# frontplatine_v0_2_230121.net
KiCad netlist of a schematic drawn in EAGLE
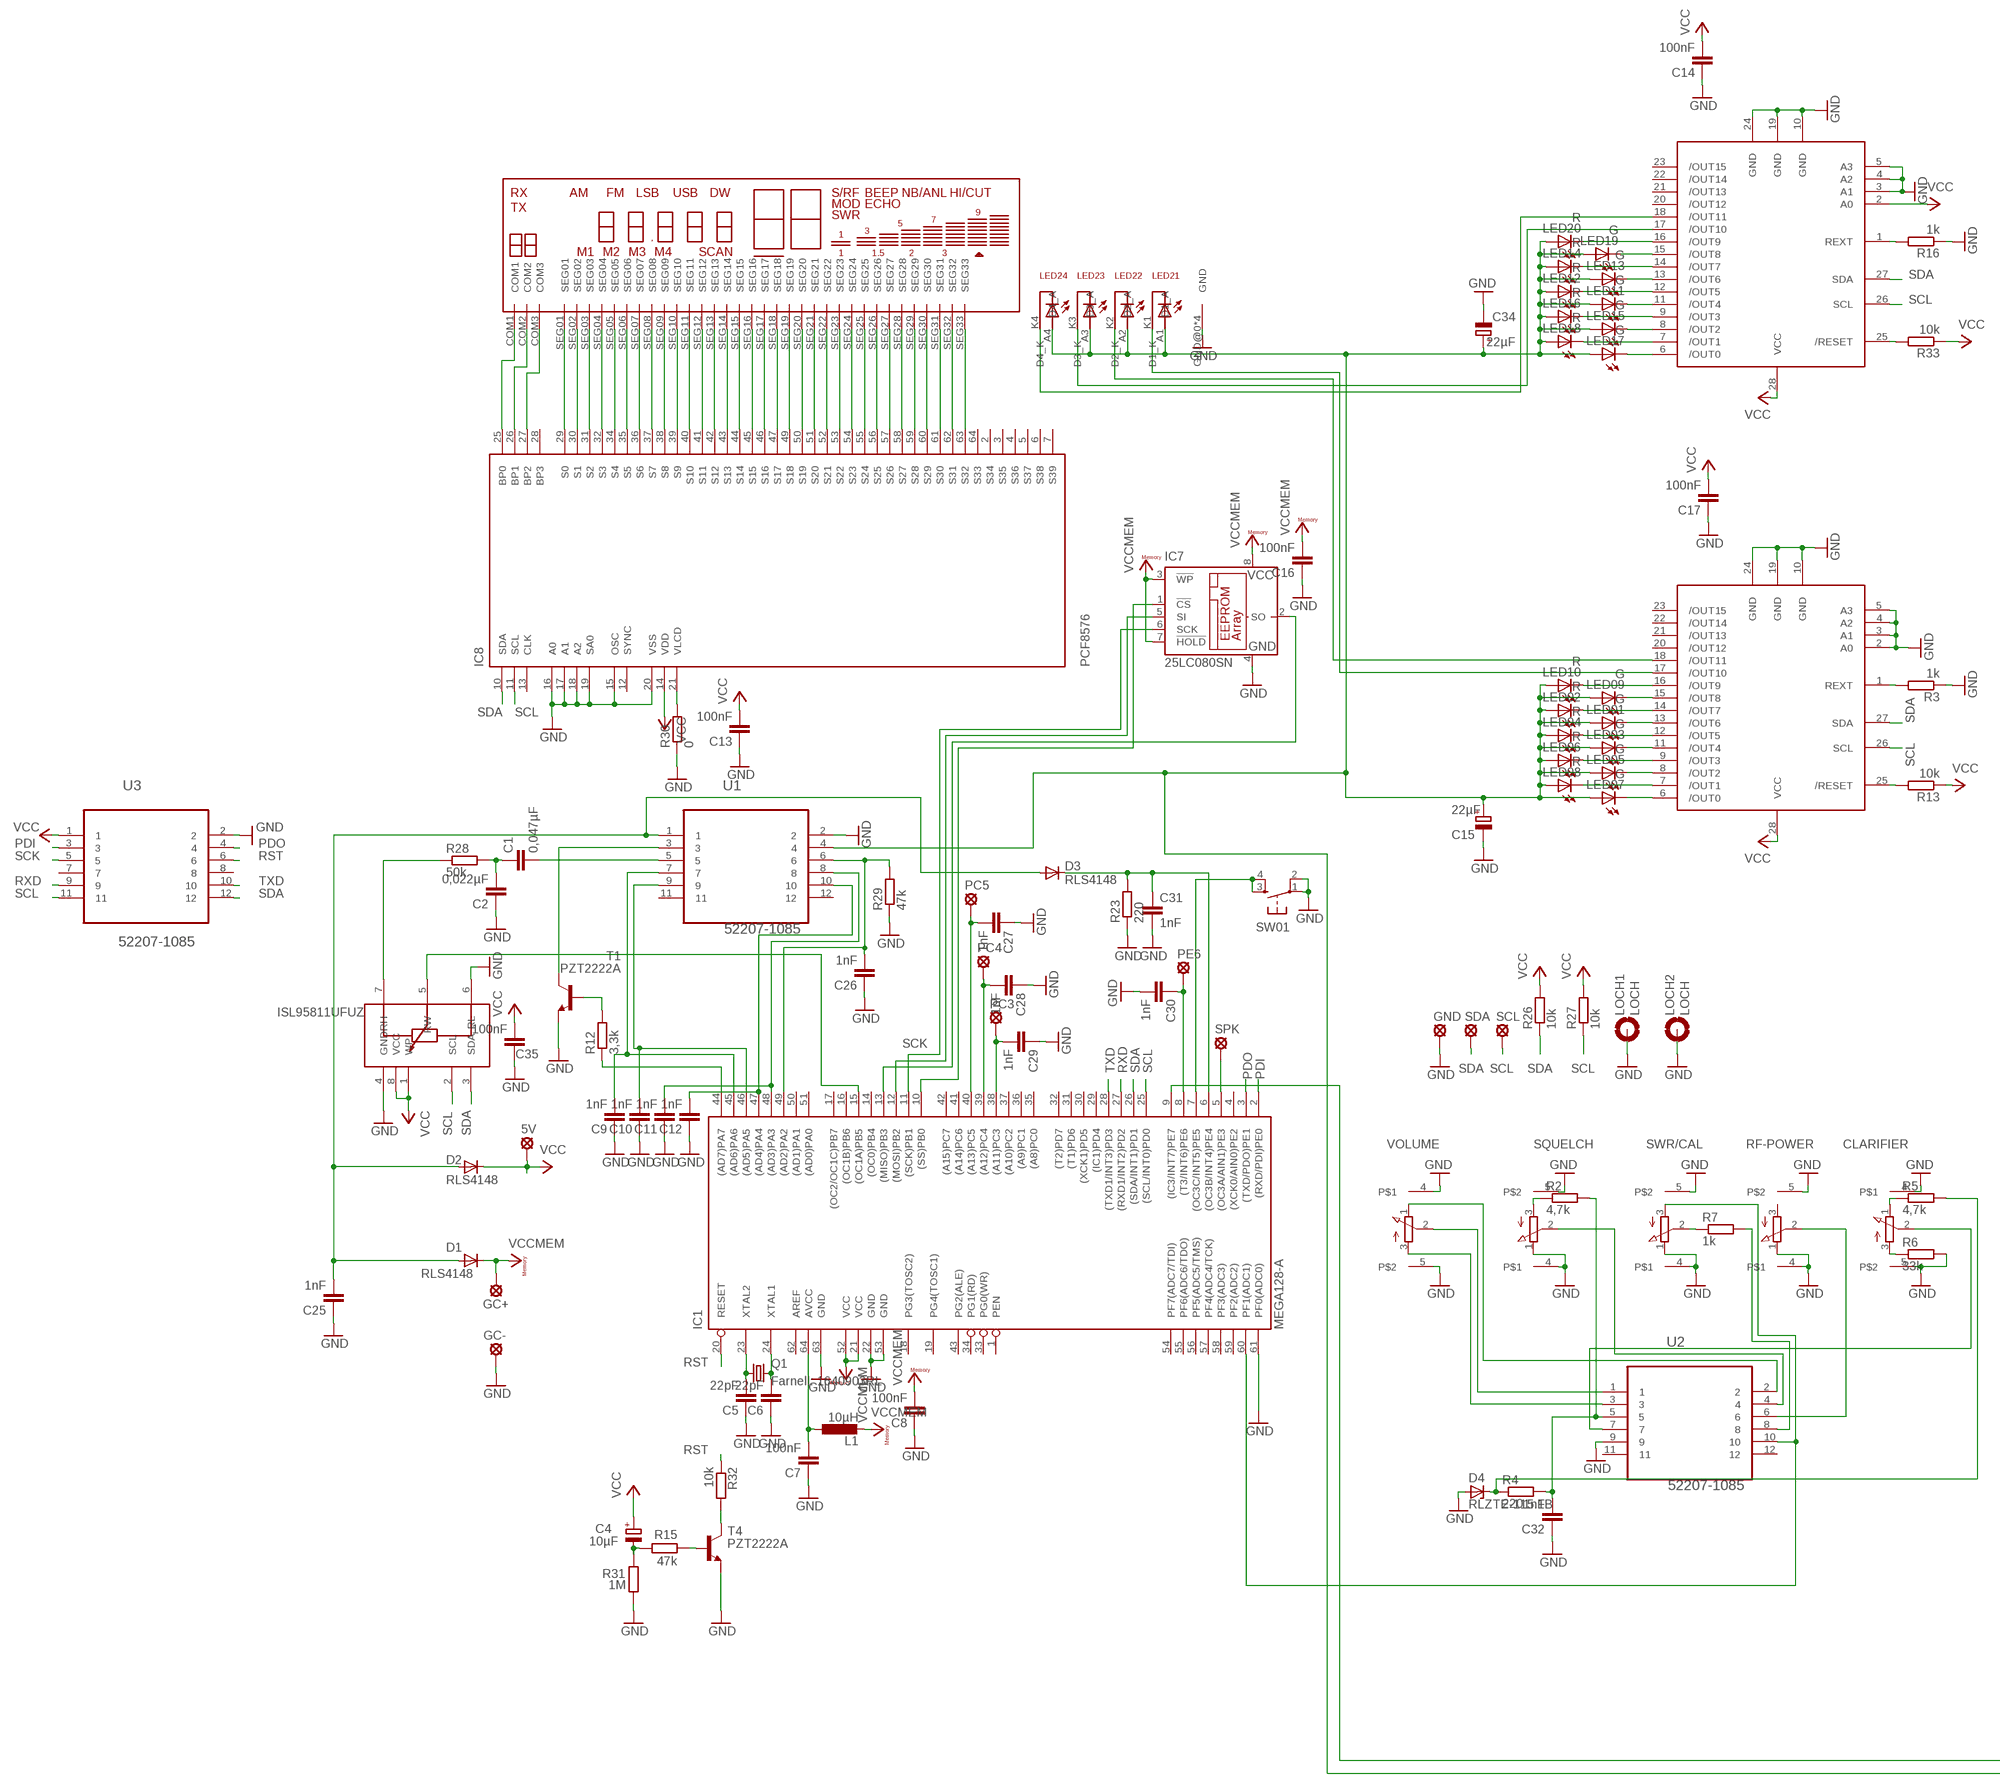
[diagram p0: schematic, sheet 1, part 1 of 2]
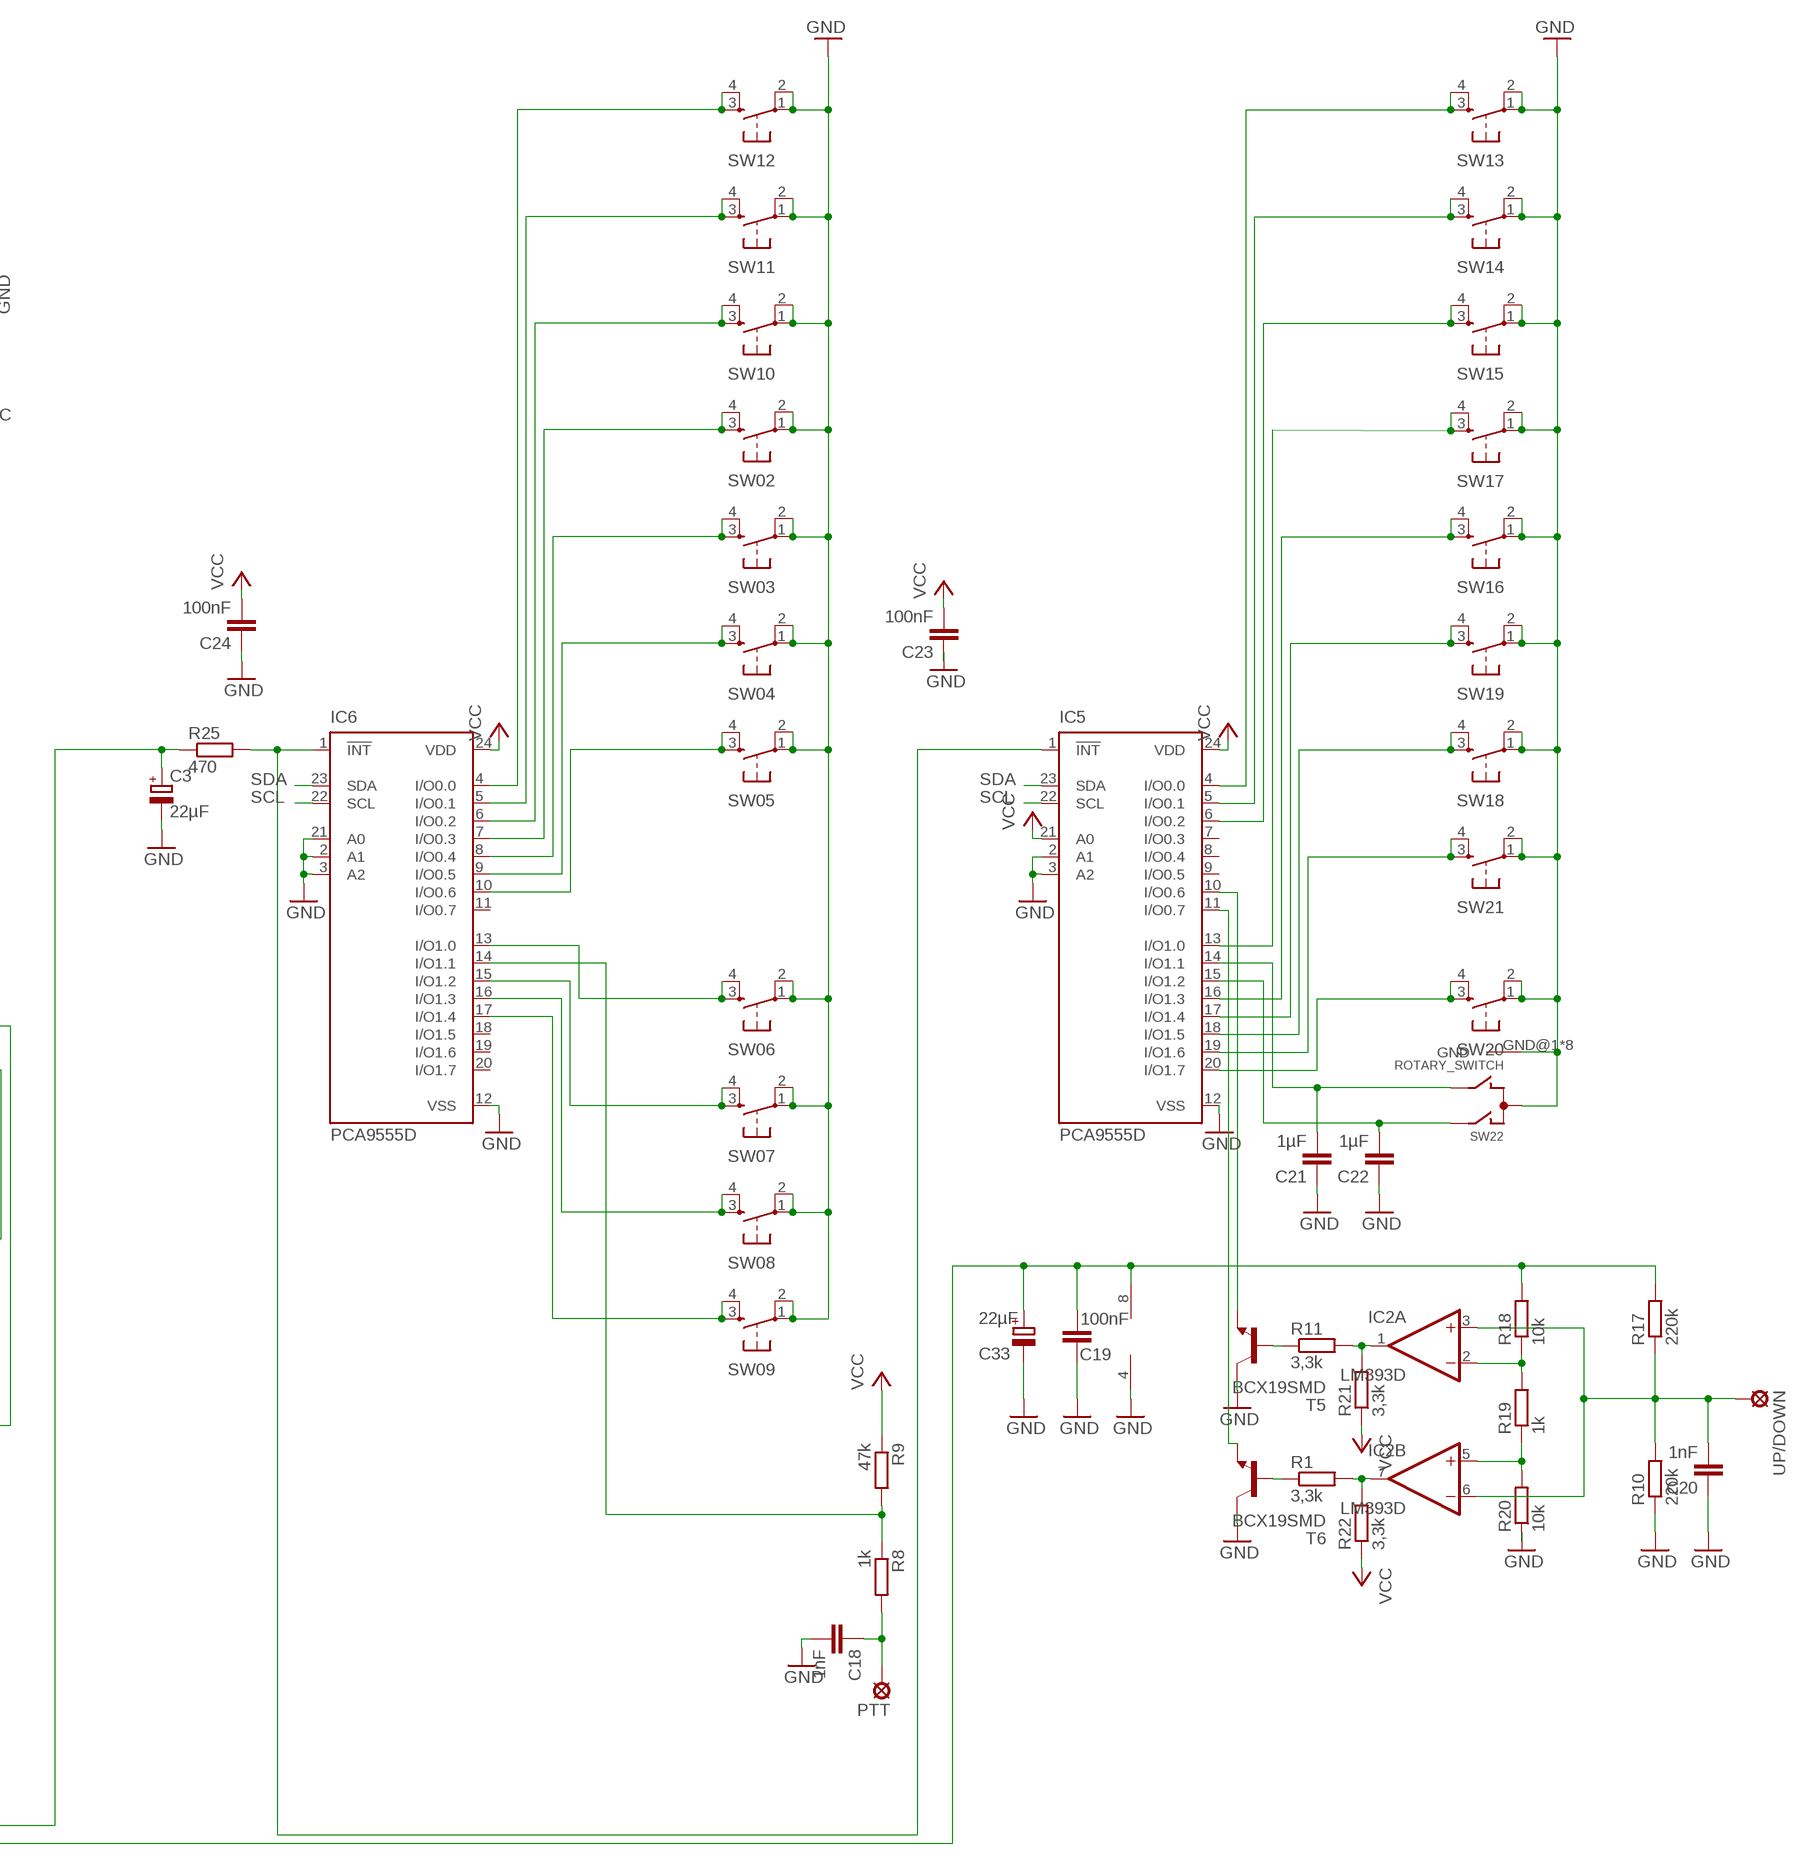
[diagram p1: schematic, sheet 1, part 2 of 2]

(export (version "E")
  (design (tool "Eeschema 10.0.6"))
  (components
    (comp (ref "5V")
      (value "SE11")
      (footprint "eagle-import:SE11")
      (libsource (lib "eagle-import") (part "SE11"))
    )
    (comp (ref "C1")
      (value "0,047µF")
      (footprint "eagle-import:C1206")
      (libsource (lib "eagle-import") (part "C-EUC1206"))
    )
    (comp (ref "C2")
      (value "0,022µF")
      (footprint "eagle-import:C1206")
      (libsource (lib "eagle-import") (part "resistor_C-EUC1206"))
    )
    (comp (ref "C3")
      (value "22µF")
      (footprint "eagle-import:CT3216")
      (libsource (lib "eagle-import") (part "CPOL-EUCT3216"))
    )
    (comp (ref "C4")
      (value "10µF")
      (footprint "eagle-import:CT3216")
      (libsource (lib "eagle-import") (part "CPOL-EUCT3216"))
    )
    (comp (ref "C5")
      (value "22pF")
      (footprint "eagle-import:C1206")
      (libsource (lib "eagle-import") (part "resistor_C-EUC1206"))
    )
    (comp (ref "C6")
      (value "22pF")
      (footprint "eagle-import:C1206")
      (libsource (lib "eagle-import") (part "resistor_C-EUC1206"))
    )
    (comp (ref "C7")
      (value "100nF")
      (footprint "eagle-import:C1206")
      (libsource (lib "eagle-import") (part "resistor_C-EUC1206"))
    )
    (comp (ref "C8")
      (value "100nF")
      (footprint "eagle-import:C1206")
      (libsource (lib "eagle-import") (part "resistor_C-EUC1206"))
    )
    (comp (ref "C9")
      (value "1nF")
      (footprint "eagle-import:C1206")
      (libsource (lib "eagle-import") (part "resistor_C-EUC1206"))
    )
    (comp (ref "C10")
      (value "1nF")
      (footprint "eagle-import:C1206")
      (libsource (lib "eagle-import") (part "resistor_C-EUC1206"))
    )
    (comp (ref "C11")
      (value "1nF")
      (footprint "eagle-import:C1206")
      (libsource (lib "eagle-import") (part "resistor_C-EUC1206"))
    )
    (comp (ref "C12")
      (value "1nF")
      (footprint "eagle-import:C1206")
      (libsource (lib "eagle-import") (part "resistor_C-EUC1206"))
    )
    (comp (ref "C13")
      (value "100nF")
      (footprint "eagle-import:C1206")
      (libsource (lib "eagle-import") (part "resistor_C-EUC1206"))
    )
    (comp (ref "C14")
      (value "100nF")
      (footprint "eagle-import:C1206")
      (libsource (lib "eagle-import") (part "resistor_C-EUC1206"))
    )
    (comp (ref "C15")
      (value "22µF")
      (footprint "eagle-import:CT3216")
      (libsource (lib "eagle-import") (part "CPOL-EUCT3216"))
    )
    (comp (ref "C16")
      (value "100nF")
      (footprint "eagle-import:C1206")
      (libsource (lib "eagle-import") (part "resistor_C-EUC1206"))
    )
    (comp (ref "C17")
      (value "100nF")
      (footprint "eagle-import:C1206")
      (libsource (lib "eagle-import") (part "resistor_C-EUC1206"))
    )
    (comp (ref "C18")
      (value "1nF")
      (footprint "eagle-import:C1206")
      (libsource (lib "eagle-import") (part "resistor_C-EUC1206"))
    )
    (comp (ref "C19")
      (value "100nF")
      (footprint "eagle-import:C1206")
      (libsource (lib "eagle-import") (part "resistor_C-EUC1206"))
    )
    (comp (ref "C20")
      (value "1nF")
      (footprint "eagle-import:C1206")
      (libsource (lib "eagle-import") (part "resistor_C-EUC1206"))
    )
    (comp (ref "C21")
      (value "1µF")
      (footprint "eagle-import:C1206")
      (libsource (lib "eagle-import") (part "resistor_C-EUC1206"))
    )
    (comp (ref "C22")
      (value "1µF")
      (footprint "eagle-import:C1206")
      (libsource (lib "eagle-import") (part "resistor_C-EUC1206"))
    )
    (comp (ref "C23")
      (value "100nF")
      (footprint "eagle-import:C1206")
      (libsource (lib "eagle-import") (part "resistor_C-EUC1206"))
    )
    (comp (ref "C24")
      (value "100nF")
      (footprint "eagle-import:C1206")
      (libsource (lib "eagle-import") (part "resistor_C-EUC1206"))
    )
    (comp (ref "C25")
      (value "1nF")
      (footprint "eagle-import:C1206")
      (libsource (lib "eagle-import") (part "resistor_C-EUC1206"))
    )
    (comp (ref "C26")
      (value "1nF")
      (footprint "eagle-import:C1206")
      (libsource (lib "eagle-import") (part "resistor_C-EUC1206"))
    )
    (comp (ref "C27")
      (value "1nF")
      (footprint "eagle-import:C1206")
      (libsource (lib "eagle-import") (part "resistor_C-EUC1206"))
    )
    (comp (ref "C28")
      (value "1nF")
      (footprint "eagle-import:C1206")
      (libsource (lib "eagle-import") (part "resistor_C-EUC1206"))
    )
    (comp (ref "C29")
      (value "1nF")
      (footprint "eagle-import:C1206")
      (libsource (lib "eagle-import") (part "resistor_C-EUC1206"))
    )
    (comp (ref "C30")
      (value "1nF")
      (footprint "eagle-import:C1206")
      (libsource (lib "eagle-import") (part "resistor_C-EUC1206"))
    )
    (comp (ref "C31")
      (value "1nF")
      (footprint "eagle-import:C1206")
      (libsource (lib "eagle-import") (part "resistor_C-EUC1206"))
    )
    (comp (ref "C32")
      (value "1nF")
      (footprint "eagle-import:C1206")
      (libsource (lib "eagle-import") (part "resistor_C-EUC1206"))
    )
    (comp (ref "C33")
      (value "22µF")
      (footprint "eagle-import:CT3216")
      (libsource (lib "eagle-import") (part "CPOL-EUCT3216"))
    )
    (comp (ref "C34")
      (value "22µF")
      (footprint "eagle-import:CT3216")
      (libsource (lib "eagle-import") (part "CPOL-EUCT3216"))
    )
    (comp (ref "C35")
      (value "100nF")
      (footprint "eagle-import:C1206")
      (libsource (lib "eagle-import") (part "resistor_C-EUC1206"))
    )
    (comp (ref "CLARIFIER")
      (value "POTI")
      (footprint "eagle-import:POTI")
      (libsource (lib "eagle-import") (part "POTI"))
    )
    (comp (ref "D1")
      (value "RLS4148")
      (footprint "eagle-import:SOD80C")
      (libsource (lib "eagle-import") (part "DIODE-SOD80C"))
    )
    (comp (ref "D2")
      (value "RLS4148")
      (footprint "eagle-import:SOD80C")
      (libsource (lib "eagle-import") (part "DIODE-SOD80C"))
    )
    (comp (ref "D3")
      (value "RLS4148")
      (footprint "eagle-import:SOD80C")
      (libsource (lib "eagle-import") (part "DIODE-SOD80C"))
    )
    (comp (ref "D4")
      (value "RLZTE-115.1B")
      (footprint "eagle-import:SOD80C")
      (libsource (lib "eagle-import") (part "ZENER-DIODESOD80C"))
    )
    (comp (ref "DISPLAY1")
      (value "DISPLAY")
      (footprint "eagle-import:DISPLAY")
      (libsource (lib "eagle-import") (part "DISPLAY"))
    )
    (comp (ref "GC+")
      (value "SE11")
      (footprint "eagle-import:SE11")
      (libsource (lib "eagle-import") (part "SE11"))
    )
    (comp (ref "GC-")
      (value "SE11")
      (footprint "eagle-import:SE11")
      (libsource (lib "eagle-import") (part "SE11"))
    )
    (comp (ref "GND")
      (value "SE11")
      (footprint "eagle-import:SE11")
      (libsource (lib "eagle-import") (part "SE11"))
    )
    (comp (ref "IC1")
      (value "MEGA128-A")
      (footprint "eagle-import:TQFP64")
      (fields (field (name "MPN") "ATMEGA128-16AU"))
      (libsource (lib "eagle-import") (part "MEGA128-A"))
    )
    (comp (ref "IC2")
      (value "LM393D")
      (footprint "eagle-import:SO08")
      (libsource (lib "eagle-import") (part "LM393D"))
    )
    (comp (ref "IC3")
      (value "TLC59116")
      (footprint "eagle-import:TSSOP28")
      (libsource (lib "eagle-import") (part "TLC59116"))
    )
    (comp (ref "IC4")
      (value "TLC59116")
      (footprint "eagle-import:TSSOP28")
      (libsource (lib "eagle-import") (part "TLC59116"))
    )
    (comp (ref "IC5")
      (value "PCA9555D")
      (footprint "eagle-import:SO24")
      (fields (field (name "MPN") "PCA9555DW"))
      (libsource (lib "eagle-import") (part "PCA9555D"))
    )
    (comp (ref "IC6")
      (value "PCA9555D")
      (footprint "eagle-import:SO24")
      (fields (field (name "MPN") "PCA9555DW"))
      (libsource (lib "eagle-import") (part "PCA9555D"))
    )
    (comp (ref "IC7")
      (value "25LC080SN")
      (footprint "eagle-import:SO-08")
      (fields
        (field (name "MF") "MICROCHIP")
        (field (name "MPN") "25LC080/SN")
        (field (name "MPN_1") "25LC080/SN")
        (field (name "OC_FARNELL") "1137302")
        (field (name "OC_NEWARK") "96K4092")
      )
      (libsource (lib "eagle-import") (part "25SNLC080"))
    )
    (comp (ref "IC8")
      (value "PCF8576")
      (footprint "eagle-import:LQFP-ST-64-2")
      (libsource (lib "eagle-import") (part "PCF8576"))
    )
    (comp (ref "L1")
      (value "10µH")
      (footprint "eagle-import:L1812")
      (libsource (lib "eagle-import") (part "L-EUL1812"))
    )
    (comp (ref "LED01")
      (value "G")
      (footprint "eagle-import:CHIPLED_1206")
      (libsource (lib "eagle-import") (part "LEDCHIPLED_1206"))
    )
    (comp (ref "LED02")
      (value "R")
      (footprint "eagle-import:CHIPLED_1206")
      (libsource (lib "eagle-import") (part "LEDCHIPLED_1206"))
    )
    (comp (ref "LED03")
      (value "G")
      (footprint "eagle-import:CHIPLED_1206")
      (libsource (lib "eagle-import") (part "LEDCHIPLED_1206"))
    )
    (comp (ref "LED04")
      (value "R")
      (footprint "eagle-import:CHIPLED_1206")
      (libsource (lib "eagle-import") (part "LEDCHIPLED_1206"))
    )
    (comp (ref "LED05")
      (value "G")
      (footprint "eagle-import:CHIPLED_1206")
      (libsource (lib "eagle-import") (part "LEDCHIPLED_1206"))
    )
    (comp (ref "LED06")
      (value "R")
      (footprint "eagle-import:CHIPLED_1206")
      (libsource (lib "eagle-import") (part "LEDCHIPLED_1206"))
    )
    (comp (ref "LED07")
      (value "G")
      (footprint "eagle-import:CHIPLED_1206")
      (libsource (lib "eagle-import") (part "LEDCHIPLED_1206"))
    )
    (comp (ref "LED08")
      (value "R")
      (footprint "eagle-import:CHIPLED_1206")
      (libsource (lib "eagle-import") (part "LEDCHIPLED_1206"))
    )
    (comp (ref "LED09")
      (value "G")
      (footprint "eagle-import:CHIPLED_1206")
      (libsource (lib "eagle-import") (part "LEDCHIPLED_1206"))
    )
    (comp (ref "LED10")
      (value "R")
      (footprint "eagle-import:CHIPLED_1206")
      (libsource (lib "eagle-import") (part "LEDCHIPLED_1206"))
    )
    (comp (ref "LED11")
      (value "G")
      (footprint "eagle-import:CHIPLED_1206")
      (libsource (lib "eagle-import") (part "LEDCHIPLED_1206"))
    )
    (comp (ref "LED12")
      (value "R")
      (footprint "eagle-import:CHIPLED_1206")
      (libsource (lib "eagle-import") (part "LEDCHIPLED_1206"))
    )
    (comp (ref "LED13")
      (value "G")
      (footprint "eagle-import:CHIPLED_1206")
      (libsource (lib "eagle-import") (part "LEDCHIPLED_1206"))
    )
    (comp (ref "LED14")
      (value "R")
      (footprint "eagle-import:CHIPLED_1206")
      (libsource (lib "eagle-import") (part "LEDCHIPLED_1206"))
    )
    (comp (ref "LED15")
      (value "G")
      (footprint "eagle-import:CHIPLED_1206")
      (libsource (lib "eagle-import") (part "LEDCHIPLED_1206"))
    )
    (comp (ref "LED16")
      (value "R")
      (footprint "eagle-import:CHIPLED_1206")
      (libsource (lib "eagle-import") (part "LEDCHIPLED_1206"))
    )
    (comp (ref "LED17")
      (value "G")
      (footprint "eagle-import:CHIPLED_1206")
      (libsource (lib "eagle-import") (part "LEDCHIPLED_1206"))
    )
    (comp (ref "LED18")
      (value "R")
      (footprint "eagle-import:CHIPLED_1206")
      (libsource (lib "eagle-import") (part "LEDCHIPLED_1206"))
    )
    (comp (ref "LED19")
      (value "G")
      (footprint "eagle-import:CHIPLED_1206")
      (libsource (lib "eagle-import") (part "LEDCHIPLED_1206"))
    )
    (comp (ref "LED20")
      (value "R")
      (footprint "eagle-import:CHIPLED_1206")
      (libsource (lib "eagle-import") (part "LEDCHIPLED_1206"))
    )
    (comp (ref "LOCH1")
      (value "LOCH")
      (footprint "eagle-import:LOCH")
      (libsource (lib "eagle-import") (part "LOCH"))
    )
    (comp (ref "LOCH2")
      (value "LOCH")
      (footprint "eagle-import:LOCH")
      (libsource (lib "eagle-import") (part "LOCH"))
    )
    (comp (ref "PC3")
      (value "SE11")
      (footprint "eagle-import:SE11")
      (libsource (lib "eagle-import") (part "SE11"))
    )
    (comp (ref "PC4")
      (value "SE11")
      (footprint "eagle-import:SE11")
      (libsource (lib "eagle-import") (part "SE11"))
    )
    (comp (ref "PC5")
      (value "SE11")
      (footprint "eagle-import:SE11")
      (libsource (lib "eagle-import") (part "SE11"))
    )
    (comp (ref "PE6")
      (value "SE11")
      (footprint "eagle-import:SE11")
      (libsource (lib "eagle-import") (part "SE11"))
    )
    (comp (ref "PTT")
      (value "SE11")
      (footprint "eagle-import:SE11")
      (libsource (lib "eagle-import") (part "SE11"))
    )
    (comp (ref "Q1")
      (value "Farnell: 1640903RL")
      (footprint "eagle-import:HC49UP")
      (libsource (lib "eagle-import") (part "CRYSTALHC49UP"))
    )
    (comp (ref "R1")
      (value "3,3k")
      (footprint "eagle-import:R1206")
      (libsource (lib "eagle-import") (part "resistor_R-EU_R1206"))
    )
    (comp (ref "R2")
      (value "4,7k")
      (footprint "eagle-import:R1206")
      (libsource (lib "eagle-import") (part "resistor_R-EU_R1206"))
    )
    (comp (ref "R3")
      (value "1k")
      (footprint "eagle-import:R1206")
      (libsource (lib "eagle-import") (part "R-EU_R1206"))
    )
    (comp (ref "R4")
      (value "220")
      (footprint "eagle-import:R1206")
      (libsource (lib "eagle-import") (part "resistor_R-EU_R1206"))
    )
    (comp (ref "R5")
      (value "4,7k")
      (footprint "eagle-import:R1206")
      (libsource (lib "eagle-import") (part "resistor_R-EU_R1206"))
    )
    (comp (ref "R6")
      (value "33k")
      (footprint "eagle-import:R1206")
      (libsource (lib "eagle-import") (part "resistor_R-EU_R1206"))
    )
    (comp (ref "R7")
      (value "1k")
      (footprint "eagle-import:R1206")
      (libsource (lib "eagle-import") (part "resistor_R-EU_R1206"))
    )
    (comp (ref "R8")
      (value "1k")
      (footprint "eagle-import:R1206")
      (libsource (lib "eagle-import") (part "resistor_R-EU_R1206"))
    )
    (comp (ref "R9")
      (value "47k")
      (footprint "eagle-import:R1206")
      (libsource (lib "eagle-import") (part "resistor_R-EU_R1206"))
    )
    (comp (ref "R10")
      (value "220k")
      (footprint "eagle-import:R1206")
      (libsource (lib "eagle-import") (part "resistor_R-EU_R1206"))
    )
    (comp (ref "R11")
      (value "3,3k")
      (footprint "eagle-import:R1206")
      (libsource (lib "eagle-import") (part "resistor_R-EU_R1206"))
    )
    (comp (ref "R12")
      (value "3,3k")
      (footprint "eagle-import:R1206")
      (libsource (lib "eagle-import") (part "resistor_R-EU_R1206"))
    )
    (comp (ref "R13")
      (value "10k")
      (footprint "eagle-import:R1206")
      (libsource (lib "eagle-import") (part "resistor_R-EU_R1206"))
    )
    (comp (ref "R15")
      (value "47k")
      (footprint "eagle-import:R1206")
      (libsource (lib "eagle-import") (part "resistor_R-EU_R1206"))
    )
    (comp (ref "R16")
      (value "1k")
      (footprint "eagle-import:R1206")
      (libsource (lib "eagle-import") (part "R-EU_R1206"))
    )
    (comp (ref "R17")
      (value "220k")
      (footprint "eagle-import:R1206")
      (libsource (lib "eagle-import") (part "resistor_R-EU_R1206"))
    )
    (comp (ref "R18")
      (value "10k")
      (footprint "eagle-import:R1206")
      (libsource (lib "eagle-import") (part "resistor_R-EU_R1206"))
    )
    (comp (ref "R19")
      (value "1k")
      (footprint "eagle-import:R1206")
      (libsource (lib "eagle-import") (part "resistor_R-EU_R1206"))
    )
    (comp (ref "R20")
      (value "10k")
      (footprint "eagle-import:R1206")
      (libsource (lib "eagle-import") (part "resistor_R-EU_R1206"))
    )
    (comp (ref "R21")
      (value "3,3k")
      (footprint "eagle-import:R1206")
      (libsource (lib "eagle-import") (part "resistor_R-EU_R1206"))
    )
    (comp (ref "R22")
      (value "3,3k")
      (footprint "eagle-import:R1206")
      (libsource (lib "eagle-import") (part "resistor_R-EU_R1206"))
    )
    (comp (ref "R23")
      (value "220")
      (footprint "eagle-import:R1206")
      (libsource (lib "eagle-import") (part "resistor_R-EU_R1206"))
    )
    (comp (ref "R25")
      (value "470")
      (footprint "eagle-import:R1206")
      (libsource (lib "eagle-import") (part "resistor_R-EU_R1206"))
    )
    (comp (ref "R26")
      (value "10k")
      (footprint "eagle-import:R1206")
      (libsource (lib "eagle-import") (part "resistor_R-EU_R1206"))
    )
    (comp (ref "R27")
      (value "10k")
      (footprint "eagle-import:R1206")
      (libsource (lib "eagle-import") (part "resistor_R-EU_R1206"))
    )
    (comp (ref "R28")
      (value "50k")
      (footprint "eagle-import:R1206")
      (libsource (lib "eagle-import") (part "resistor_R-EU_R1206"))
    )
    (comp (ref "R29")
      (value "47k")
      (footprint "eagle-import:R1206")
      (libsource (lib "eagle-import") (part "resistor_R-EU_R1206"))
    )
    (comp (ref "R30")
      (value "0")
      (footprint "eagle-import:R1206")
      (libsource (lib "eagle-import") (part "resistor_R-EU_R1206"))
    )
    (comp (ref "R31")
      (value "1M")
      (footprint "eagle-import:R1206")
      (libsource (lib "eagle-import") (part "resistor_R-EU_R1206"))
    )
    (comp (ref "R32")
      (value "10k")
      (footprint "eagle-import:R1206")
      (libsource (lib "eagle-import") (part "resistor_R-EU_R1206"))
    )
    (comp (ref "R33")
      (value "10k")
      (footprint "eagle-import:R1206")
      (libsource (lib "eagle-import") (part "resistor_R-EU_R1206"))
    )
    (comp (ref "RF-POWER")
      (value "POTI")
      (footprint "eagle-import:POTI")
      (libsource (lib "eagle-import") (part "POTI"))
    )
    (comp (ref "SCL")
      (value "SE11")
      (footprint "eagle-import:SE11")
      (libsource (lib "eagle-import") (part "SE11"))
    )
    (comp (ref "SDA")
      (value "SE11")
      (footprint "eagle-import:SE11")
      (libsource (lib "eagle-import") (part "SE11"))
    )
    (comp (ref "SPK")
      (value "SE11")
      (footprint "eagle-import:SE11")
      (libsource (lib "eagle-import") (part "SE11"))
    )
    (comp (ref "SQUELCH")
      (value "POTI")
      (footprint "eagle-import:POTI")
      (libsource (lib "eagle-import") (part "POTI"))
    )
    (comp (ref "SW01")
      (value "TASTER")
      (footprint "eagle-import:TASTER")
      (libsource (lib "eagle-import") (part "TASTER"))
    )
    (comp (ref "SW02")
      (value "TASTER")
      (footprint "eagle-import:TASTER")
      (libsource (lib "eagle-import") (part "TASTER"))
    )
    (comp (ref "SW03")
      (value "TASTER")
      (footprint "eagle-import:TASTER")
      (libsource (lib "eagle-import") (part "TASTER"))
    )
    (comp (ref "SW04")
      (value "TASTER")
      (footprint "eagle-import:TASTER")
      (libsource (lib "eagle-import") (part "TASTER"))
    )
    (comp (ref "SW05")
      (value "TASTER")
      (footprint "eagle-import:TASTER")
      (libsource (lib "eagle-import") (part "TASTER"))
    )
    (comp (ref "SW06")
      (value "TASTER")
      (footprint "eagle-import:TASTER")
      (libsource (lib "eagle-import") (part "TASTER"))
    )
    (comp (ref "SW07")
      (value "TASTER")
      (footprint "eagle-import:TASTER")
      (libsource (lib "eagle-import") (part "TASTER"))
    )
    (comp (ref "SW08")
      (value "TASTER")
      (footprint "eagle-import:TASTER")
      (libsource (lib "eagle-import") (part "TASTER"))
    )
    (comp (ref "SW09")
      (value "TASTER")
      (footprint "eagle-import:TASTER")
      (libsource (lib "eagle-import") (part "TASTER"))
    )
    (comp (ref "SW10")
      (value "TASTER")
      (footprint "eagle-import:TASTER")
      (libsource (lib "eagle-import") (part "TASTER"))
    )
    (comp (ref "SW11")
      (value "TASTER")
      (footprint "eagle-import:TASTER")
      (libsource (lib "eagle-import") (part "TASTER"))
    )
    (comp (ref "SW12")
      (value "TASTER")
      (footprint "eagle-import:TASTER")
      (libsource (lib "eagle-import") (part "TASTER"))
    )
    (comp (ref "SW13")
      (value "TASTER")
      (footprint "eagle-import:TASTER")
      (libsource (lib "eagle-import") (part "TASTER"))
    )
    (comp (ref "SW14")
      (value "TASTER")
      (footprint "eagle-import:TASTER")
      (libsource (lib "eagle-import") (part "TASTER"))
    )
    (comp (ref "SW15")
      (value "TASTER")
      (footprint "eagle-import:TASTER")
      (libsource (lib "eagle-import") (part "TASTER"))
    )
    (comp (ref "SW16")
      (value "TASTER")
      (footprint "eagle-import:TASTER")
      (libsource (lib "eagle-import") (part "TASTER"))
    )
    (comp (ref "SW17")
      (value "TASTER")
      (footprint "eagle-import:TASTER")
      (libsource (lib "eagle-import") (part "TASTER"))
    )
    (comp (ref "SW18")
      (value "TASTER")
      (footprint "eagle-import:TASTER")
      (libsource (lib "eagle-import") (part "TASTER"))
    )
    (comp (ref "SW19")
      (value "TASTER")
      (footprint "eagle-import:TASTER")
      (libsource (lib "eagle-import") (part "TASTER"))
    )
    (comp (ref "SW20")
      (value "TASTER")
      (footprint "eagle-import:TASTER")
      (libsource (lib "eagle-import") (part "TASTER"))
    )
    (comp (ref "SW21")
      (value "TASTER")
      (footprint "eagle-import:TASTER")
      (libsource (lib "eagle-import") (part "TASTER"))
    )
    (comp (ref "SW22")
      (value "ROTARY_SWITCH")
      (footprint "eagle-import:ROTARY_SWITCH")
      (libsource (lib "eagle-import") (part "ROTARY_SWITCH"))
    )
    (comp (ref "SWR/CAL")
      (value "POTI")
      (footprint "eagle-import:POTI")
      (libsource (lib "eagle-import") (part "POTI"))
    )
    (comp (ref "T1")
      (value "PZT2222A")
      (footprint "eagle-import:SOT223")
      (libsource (lib "eagle-import") (part "-NPN-SOT223PZT2222A"))
    )
    (comp (ref "T4")
      (value "PZT2222A")
      (footprint "eagle-import:SOT223")
      (libsource (lib "eagle-import") (part "-NPN-SOT223PZT2222A"))
    )
    (comp (ref "T5")
      (value "BCX19SMD")
      (footprint "eagle-import:SOT23-BEC")
      (libsource (lib "eagle-import") (part "BCX19SMD"))
    )
    (comp (ref "T6")
      (value "BCX19SMD")
      (footprint "eagle-import:SOT23-BEC")
      (libsource (lib "eagle-import") (part "BCX19SMD"))
    )
    (comp (ref "U$1")
      (value "ISL95811UFUZ")
      (footprint "eagle-import:MSOP8")
      (libsource (lib "eagle-import") (part "ISL95811UFUZ"))
    )
    (comp (ref "U1")
      (value "52207-1085")
      (footprint "eagle-import:MOLEX_52207-1085")
      (fields
        (field (name "MPN") "52207-1085")
        (field (name "OC_FARNELL") "1079938")
        (field (name "OC_NEWARK") "58J9503")
        (field (name "PACKAGE") "SOCKET FPC, SMT, 1MM, 10 WAY")
      )
      (libsource (lib "eagle-import") (part "52207-1085"))
    )
    (comp (ref "U2")
      (value "52207-1085")
      (footprint "eagle-import:MOLEX_52207-1085")
      (fields
        (field (name "MPN") "52207-1085")
        (field (name "OC_FARNELL") "1079938")
        (field (name "OC_NEWARK") "58J9503")
        (field (name "PACKAGE") "SOCKET FPC, SMT, 1MM, 10 WAY")
      )
      (libsource (lib "eagle-import") (part "52207-1085"))
    )
    (comp (ref "U3")
      (value "52207-1085")
      (footprint "eagle-import:MOLEX_52207-1085")
      (libsource (lib "eagle-import") (part "52207-1085"))
    )
    (comp (ref "UP/DOWN")
      (value "SE11")
      (footprint "eagle-import:SE11")
      (libsource (lib "eagle-import") (part "SE11"))
    )
    (comp (ref "VOLUME")
      (value "POTI")
      (footprint "eagle-import:POTI")
      (libsource (lib "eagle-import") (part "POTI"))
    )
  )
  (nets
    (net (code "1") (name "/PDI") (class "Default")
      (node (ref "IC1") (pin "2") (pinfunction "(RXD/PDI)PE0_2") (pintype "bidirectional"))
      (node (ref "U3") (pin "3") (pinfunction "3_3") (pintype "passive"))
    )
    (net (code "2") (name "/PDO") (class "Default")
      (node (ref "IC1") (pin "3") (pinfunction "(TXD/PDO)PE1_3") (pintype "bidirectional"))
      (node (ref "U3") (pin "4") (pinfunction "4_4") (pintype "passive"))
    )
    (net (code "3") (name "/RST") (class "Default")
      (node (ref "IC1") (pin "20") (pinfunction "RESET_20") (pintype "input"))
      (node (ref "R32") (pin "1") (pinfunction "1_1") (pintype "passive"))
      (node (ref "U3") (pin "6") (pinfunction "6_6") (pintype "passive"))
    )
    (net (code "4") (name "/RXD") (class "Default")
      (node (ref "IC1") (pin "27") (pinfunction "(RXD1/INT2)PD2_27") (pintype "bidirectional"))
      (node (ref "U3") (pin "9") (pinfunction "9_9") (pintype "passive"))
    )
    (net (code "5") (name "/SCK") (class "Default")
      (node (ref "IC1") (pin "11") (pinfunction "(SCK)PB1_11") (pintype "bidirectional"))
      (node (ref "IC7") (pin "6") (pinfunction "SCK_6") (pintype "input"))
      (node (ref "U3") (pin "5") (pinfunction "5_5") (pintype "passive"))
    )
    (net (code "6") (name "/SCL") (class "Default")
      (node (ref "IC1") (pin "25") (pinfunction "(SCL/INT0)PD0_25") (pintype "bidirectional"))
      (node (ref "IC3") (pin "26") (pinfunction "SCL_26") (pintype "bidirectional"))
      (node (ref "IC4") (pin "26") (pinfunction "SCL_26") (pintype "bidirectional"))
      (node (ref "IC5") (pin "22") (pinfunction "SCL_22") (pintype "input"))
      (node (ref "IC6") (pin "22") (pinfunction "SCL_22") (pintype "input"))
      (node (ref "IC8") (pin "11") (pinfunction "SCL_11") (pintype "input"))
      (node (ref "R27") (pin "1") (pinfunction "1_1") (pintype "passive"))
      (node (ref "SCL") (pin "MP") (pinfunction "MP_MP") (pintype "passive"))
      (node (ref "U$1") (pin "2") (pinfunction "SCL_2") (pintype "bidirectional"))
      (node (ref "U3") (pin "11") (pinfunction "11_11") (pintype "passive"))
    )
    (net (code "7") (name "/SDA") (class "Default")
      (node (ref "IC1") (pin "26") (pinfunction "(SDA/INT1)PD1_26") (pintype "bidirectional"))
      (node (ref "IC3") (pin "27") (pinfunction "SDA_27") (pintype "bidirectional"))
      (node (ref "IC4") (pin "27") (pinfunction "SDA_27") (pintype "bidirectional"))
      (node (ref "IC5") (pin "23") (pinfunction "SDA_23") (pintype "bidirectional"))
      (node (ref "IC6") (pin "23") (pinfunction "SDA_23") (pintype "bidirectional"))
      (node (ref "IC8") (pin "10") (pinfunction "SDA_10") (pintype "bidirectional"))
      (node (ref "R26") (pin "1") (pinfunction "1_1") (pintype "passive"))
      (node (ref "SDA") (pin "MP") (pinfunction "MP_MP") (pintype "passive"))
      (node (ref "U$1") (pin "3") (pinfunction "SDA_3") (pintype "input"))
      (node (ref "U3") (pin "12") (pinfunction "12_12") (pintype "passive"))
    )
    (net (code "8") (name "/TXD") (class "Default")
      (node (ref "IC1") (pin "28") (pinfunction "(TXD1/INT3)PD3_28") (pintype "bidirectional"))
      (node (ref "U3") (pin "10") (pinfunction "10_10") (pintype "passive"))
    )
    (net (code "9") (name "GND") (class "Default")
      (node (ref "C10") (pin "1") (pinfunction "1_1") (pintype "passive"))
      (node (ref "C11") (pin "1") (pinfunction "1_1") (pintype "passive"))
      (node (ref "C12") (pin "1") (pinfunction "1_1") (pintype "passive"))
      (node (ref "C13") (pin "1") (pinfunction "1_1") (pintype "passive"))
      (node (ref "C14") (pin "1") (pinfunction "1_1") (pintype "passive"))
      (node (ref "C15") (pin "-") (pinfunction "-_-") (pintype "passive"))
      (node (ref "C16") (pin "1") (pinfunction "1_1") (pintype "passive"))
      (node (ref "C17") (pin "1") (pinfunction "1_1") (pintype "passive"))
      (node (ref "C18") (pin "2") (pinfunction "2_2") (pintype "passive"))
      (node (ref "C19") (pin "1") (pinfunction "1_1") (pintype "passive"))
      (node (ref "C2") (pin "1") (pinfunction "1_1") (pintype "passive"))
      (node (ref "C20") (pin "1") (pinfunction "1_1") (pintype "passive"))
      (node (ref "C21") (pin "1") (pinfunction "1_1") (pintype "passive"))
      (node (ref "C22") (pin "1") (pinfunction "1_1") (pintype "passive"))
      (node (ref "C23") (pin "1") (pinfunction "1_1") (pintype "passive"))
      (node (ref "C24") (pin "1") (pinfunction "1_1") (pintype "passive"))
      (node (ref "C25") (pin "1") (pinfunction "1_1") (pintype "passive"))
      (node (ref "C26") (pin "1") (pinfunction "1_1") (pintype "passive"))
      (node (ref "C27") (pin "1") (pinfunction "1_1") (pintype "passive"))
      (node (ref "C28") (pin "1") (pinfunction "1_1") (pintype "passive"))
      (node (ref "C29") (pin "1") (pinfunction "1_1") (pintype "passive"))
      (node (ref "C3") (pin "-") (pinfunction "-_-") (pintype "passive"))
      (node (ref "C30") (pin "2") (pinfunction "2_2") (pintype "passive"))
      (node (ref "C31") (pin "2") (pinfunction "2_2") (pintype "passive"))
      (node (ref "C32") (pin "1") (pinfunction "1_1") (pintype "passive"))
      (node (ref "C33") (pin "-") (pinfunction "-_-") (pintype "passive"))
      (node (ref "C34") (pin "-") (pinfunction "-_-") (pintype "passive"))
      (node (ref "C35") (pin "1") (pinfunction "1_1") (pintype "passive"))
      (node (ref "C5") (pin "1") (pinfunction "1_1") (pintype "passive"))
      (node (ref "C6") (pin "1") (pinfunction "1_1") (pintype "passive"))
      (node (ref "C7") (pin "1") (pinfunction "1_1") (pintype "passive"))
      (node (ref "C8") (pin "1") (pinfunction "1_1") (pintype "passive"))
      (node (ref "C9") (pin "1") (pinfunction "1_1") (pintype "passive"))
      (node (ref "CLARIFIER") (pin "4") (pinfunction "P$1_4") (pintype "power_in"))
      (node (ref "CLARIFIER") (pin "5") (pinfunction "P$2_5") (pintype "power_in"))
      (node (ref "D4") (pin "A") (pinfunction "A_A") (pintype "passive"))
      (node (ref "DISPLAY1") (pin "GND@0") (pinfunction "GND_GND@0") (pintype "power_in"))
      (node (ref "DISPLAY1") (pin "GND@3") (pinfunction "GND_GND@3") (pintype "power_in"))
      (node (ref "DISPLAY1") (pin "GND@6") (pinfunction "GND_GND@6") (pintype "power_in"))
      (node (ref "DISPLAY1") (pin "GND@7") (pinfunction "GND_GND@7") (pintype "power_in"))
      (node (ref "GC-") (pin "MP") (pinfunction "MP_MP") (pintype "passive"))
      (node (ref "GND") (pin "MP") (pinfunction "MP_MP") (pintype "passive"))
      (node (ref "IC1") (pin "22") (pinfunction "GND_22") (pintype "power_in"))
      (node (ref "IC1") (pin "53") (pinfunction "GND_53") (pintype "power_in"))
      (node (ref "IC1") (pin "61") (pinfunction "PF0(ADC0)_61") (pintype "input"))
      (node (ref "IC1") (pin "63") (pinfunction "GND_63") (pintype "power_in"))
      (node (ref "IC2") (pin "4") (pinfunction "V-_4") (pintype "power_in"))
      (node (ref "IC3") (pin "10") (pinfunction "GND_10") (pintype "bidirectional"))
      (node (ref "IC3") (pin "19") (pinfunction "GND_19") (pintype "bidirectional"))
      (node (ref "IC3") (pin "2") (pinfunction "A0_2") (pintype "bidirectional"))
      (node (ref "IC3") (pin "24") (pinfunction "GND_24") (pintype "bidirectional"))
      (node (ref "IC3") (pin "3") (pinfunction "A1_3") (pintype "bidirectional"))
      (node (ref "IC3") (pin "4") (pinfunction "A2_4") (pintype "bidirectional"))
      (node (ref "IC3") (pin "5") (pinfunction "A3_5") (pintype "bidirectional"))
      (node (ref "IC4") (pin "10") (pinfunction "GND_10") (pintype "bidirectional"))
      (node (ref "IC4") (pin "19") (pinfunction "GND_19") (pintype "bidirectional"))
      (node (ref "IC4") (pin "24") (pinfunction "GND_24") (pintype "bidirectional"))
      (node (ref "IC4") (pin "3") (pinfunction "A1_3") (pintype "bidirectional"))
      (node (ref "IC4") (pin "4") (pinfunction "A2_4") (pintype "bidirectional"))
      (node (ref "IC4") (pin "5") (pinfunction "A3_5") (pintype "bidirectional"))
      (node (ref "IC5") (pin "12") (pinfunction "VSS_12") (pintype "power_in"))
      (node (ref "IC5") (pin "2") (pinfunction "A1_2") (pintype "input"))
      (node (ref "IC5") (pin "3") (pinfunction "A2_3") (pintype "input"))
      (node (ref "IC6") (pin "12") (pinfunction "VSS_12") (pintype "power_in"))
      (node (ref "IC6") (pin "2") (pinfunction "A1_2") (pintype "input"))
      (node (ref "IC6") (pin "21") (pinfunction "A0_21") (pintype "input"))
      (node (ref "IC6") (pin "3") (pinfunction "A2_3") (pintype "input"))
      (node (ref "IC7") (pin "4") (pinfunction "GND_4") (pintype "power_in"))
      (node (ref "IC8") (pin "15") (pinfunction "OSC_15") (pintype "input"))
      (node (ref "IC8") (pin "16") (pinfunction "A0_16") (pintype "input"))
      (node (ref "IC8") (pin "17") (pinfunction "A1_17") (pintype "input"))
      (node (ref "IC8") (pin "18") (pinfunction "A2_18") (pintype "input"))
      (node (ref "IC8") (pin "19") (pinfunction "SA0_19") (pintype "input"))
      (node (ref "IC8") (pin "20") (pinfunction "VSS_20") (pintype "power_in"))
      (node (ref "LOCH1") (pin "B3,0") (pinfunction "MOUNT_B3,0") (pintype "passive"))
      (node (ref "LOCH2") (pin "B3,0") (pinfunction "MOUNT_B3,0") (pintype "passive"))
      (node (ref "R10") (pin "1") (pinfunction "1_1") (pintype "passive"))
      (node (ref "R16") (pin "1") (pinfunction "1_1") (pintype "passive"))
      (node (ref "R20") (pin "1") (pinfunction "1_1") (pintype "passive"))
      (node (ref "R23") (pin "1") (pinfunction "1_1") (pintype "passive"))
      (node (ref "R29") (pin "1") (pinfunction "1_1") (pintype "passive"))
      (node (ref "R3") (pin "1") (pinfunction "1_1") (pintype "passive"))
      (node (ref "R30") (pin "1") (pinfunction "1_1") (pintype "passive"))
      (node (ref "R31") (pin "2") (pinfunction "2_2") (pintype "passive"))
      (node (ref "R6") (pin "2") (pinfunction "2_2") (pintype "passive"))
      (node (ref "RF-POWER") (pin "1") (pinfunction "E_1") (pintype "passive"))
      (node (ref "RF-POWER") (pin "4") (pinfunction "P$1_4") (pintype "power_in"))
      (node (ref "RF-POWER") (pin "5") (pinfunction "P$2_5") (pintype "power_in"))
      (node (ref "SQUELCH") (pin "1") (pinfunction "E_1") (pintype "passive"))
      (node (ref "SQUELCH") (pin "4") (pinfunction "P$1_4") (pintype "power_in"))
      (node (ref "SQUELCH") (pin "5") (pinfunction "P$2_5") (pintype "power_in"))
      (node (ref "SW01") (pin "1") (pinfunction "1_1") (pintype "passive"))
      (node (ref "SW01") (pin "2") (pinfunction "2_2") (pintype "passive"))
      (node (ref "SW02") (pin "1") (pinfunction "1_1") (pintype "passive"))
      (node (ref "SW02") (pin "2") (pinfunction "2_2") (pintype "passive"))
      (node (ref "SW03") (pin "1") (pinfunction "1_1") (pintype "passive"))
      (node (ref "SW03") (pin "2") (pinfunction "2_2") (pintype "passive"))
      (node (ref "SW04") (pin "1") (pinfunction "1_1") (pintype "passive"))
      (node (ref "SW04") (pin "2") (pinfunction "2_2") (pintype "passive"))
      (node (ref "SW05") (pin "1") (pinfunction "1_1") (pintype "passive"))
      (node (ref "SW05") (pin "2") (pinfunction "2_2") (pintype "passive"))
      (node (ref "SW06") (pin "1") (pinfunction "1_1") (pintype "passive"))
      (node (ref "SW06") (pin "2") (pinfunction "2_2") (pintype "passive"))
      (node (ref "SW07") (pin "1") (pinfunction "1_1") (pintype "passive"))
      (node (ref "SW07") (pin "2") (pinfunction "2_2") (pintype "passive"))
      (node (ref "SW08") (pin "1") (pinfunction "1_1") (pintype "passive"))
      (node (ref "SW08") (pin "2") (pinfunction "2_2") (pintype "passive"))
      (node (ref "SW09") (pin "1") (pinfunction "1_1") (pintype "passive"))
      (node (ref "SW09") (pin "2") (pinfunction "2_2") (pintype "passive"))
      (node (ref "SW10") (pin "1") (pinfunction "1_1") (pintype "passive"))
      (node (ref "SW10") (pin "2") (pinfunction "2_2") (pintype "passive"))
      (node (ref "SW11") (pin "1") (pinfunction "1_1") (pintype "passive"))
      (node (ref "SW11") (pin "2") (pinfunction "2_2") (pintype "passive"))
      (node (ref "SW12") (pin "1") (pinfunction "1_1") (pintype "passive"))
      (node (ref "SW12") (pin "2") (pinfunction "2_2") (pintype "passive"))
      (node (ref "SW13") (pin "1") (pinfunction "1_1") (pintype "passive"))
      (node (ref "SW13") (pin "2") (pinfunction "2_2") (pintype "passive"))
      (node (ref "SW14") (pin "1") (pinfunction "1_1") (pintype "passive"))
      (node (ref "SW14") (pin "2") (pinfunction "2_2") (pintype "passive"))
      (node (ref "SW15") (pin "1") (pinfunction "1_1") (pintype "passive"))
      (node (ref "SW15") (pin "2") (pinfunction "2_2") (pintype "passive"))
      (node (ref "SW16") (pin "1") (pinfunction "1_1") (pintype "passive"))
      (node (ref "SW16") (pin "2") (pinfunction "2_2") (pintype "passive"))
      (node (ref "SW17") (pin "1") (pinfunction "1_1") (pintype "passive"))
      (node (ref "SW17") (pin "2") (pinfunction "2_2") (pintype "passive"))
      (node (ref "SW18") (pin "1") (pinfunction "1_1") (pintype "passive"))
      (node (ref "SW18") (pin "2") (pinfunction "2_2") (pintype "passive"))
      (node (ref "SW19") (pin "1") (pinfunction "1_1") (pintype "passive"))
      (node (ref "SW19") (pin "2") (pinfunction "2_2") (pintype "passive"))
      (node (ref "SW20") (pin "1") (pinfunction "1_1") (pintype "passive"))
      (node (ref "SW20") (pin "2") (pinfunction "2_2") (pintype "passive"))
      (node (ref "SW21") (pin "1") (pinfunction "1_1") (pintype "passive"))
      (node (ref "SW21") (pin "2") (pinfunction "2_2") (pintype "passive"))
      (node (ref "SW22") (pin "C") (pinfunction "C_C") (pintype "passive"))
      (node (ref "SW22") (pin "GND@1") (pinfunction "GND_GND@1") (pintype "power_in"))
      (node (ref "SW22") (pin "GND@2") (pinfunction "GND_GND@2") (pintype "power_in"))
      (node (ref "SW22") (pin "GND@3") (pinfunction "GND_GND@3") (pintype "power_in"))
      (node (ref "SW22") (pin "GND@4") (pinfunction "GND_GND@4") (pintype "power_in"))
      (node (ref "SW22") (pin "GND@5") (pinfunction "GND_GND@5") (pintype "power_in"))
      (node (ref "SW22") (pin "GND@6") (pinfunction "GND_GND@6") (pintype "power_in"))
      (node (ref "SW22") (pin "GND@7") (pinfunction "GND_GND@7") (pintype "power_in"))
      (node (ref "SW22") (pin "GND@8") (pinfunction "GND_GND@8") (pintype "power_in"))
      (node (ref "SWR/CAL") (pin "1") (pinfunction "E_1") (pintype "passive"))
      (node (ref "SWR/CAL") (pin "4") (pinfunction "P$1_4") (pintype "power_in"))
      (node (ref "SWR/CAL") (pin "5") (pinfunction "P$2_5") (pintype "power_in"))
      (node (ref "T1") (pin "3") (pinfunction "E_3") (pintype "passive"))
      (node (ref "T4") (pin "3") (pinfunction "E_3") (pintype "passive"))
      (node (ref "T5") (pin "C") (pinfunction "C_C") (pintype "passive"))
      (node (ref "T6") (pin "C") (pinfunction "C_C") (pintype "passive"))
      (node (ref "U$1") (pin "4") (pinfunction "GND_4") (pintype "power_in"))
      (node (ref "U$1") (pin "6") (pinfunction "RL_6") (pintype "bidirectional"))
      (node (ref "U1") (pin "2") (pinfunction "2_2") (pintype "passive"))
      (node (ref "U2") (pin "9") (pinfunction "9_9") (pintype "passive"))
      (node (ref "U3") (pin "2") (pinfunction "2_2") (pintype "passive"))
      (node (ref "VOLUME") (pin "4") (pinfunction "P$1_4") (pintype "power_in"))
      (node (ref "VOLUME") (pin "5") (pinfunction "P$2_5") (pintype "power_in"))
    )
    (net (code "10") (name "Net-(C1-Pad1)") (class "Default")
      (node (ref "C1") (pin "1") (pinfunction "1_1") (pintype "passive"))
      (node (ref "C2") (pin "2") (pinfunction "2_2") (pintype "passive"))
      (node (ref "R28") (pin "2") (pinfunction "2_2") (pintype "passive"))
    )
    (net (code "11") (name "Net-(C1-Pad2)") (class "Default")
      (node (ref "C1") (pin "2") (pinfunction "2_2") (pintype "passive"))
      (node (ref "U1") (pin "5") (pinfunction "5_5") (pintype "passive"))
    )
    (net (code "12") (name "Net-(C4-Pad-)") (class "Default")
      (node (ref "C4") (pin "-") (pinfunction "-_-") (pintype "passive"))
      (node (ref "R15") (pin "2") (pinfunction "2_2") (pintype "passive"))
      (node (ref "R31") (pin "1") (pinfunction "1_1") (pintype "passive"))
    )
    (net (code "13") (name "Net-(C18-Pad1)") (class "Default")
      (node (ref "C18") (pin "1") (pinfunction "1_1") (pintype "passive"))
      (node (ref "PTT") (pin "MP") (pinfunction "MP_MP") (pintype "passive"))
      (node (ref "R8") (pin "2") (pinfunction "2_2") (pintype "passive"))
    )
    (net (code "14") (name "Net-(C25-Pad2)") (class "Default")
      (node (ref "C25") (pin "2") (pinfunction "2_2") (pintype "passive"))
      (node (ref "D1") (pin "A") (pinfunction "A_A") (pintype "passive"))
      (node (ref "D2") (pin "A") (pinfunction "A_A") (pintype "passive"))
      (node (ref "D3") (pin "A") (pinfunction "A_A") (pintype "passive"))
      (node (ref "U1") (pin "1") (pinfunction "1_1") (pintype "passive"))
    )
    (net (code "15") (name "Net-(C32-Pad2)") (class "Default")
      (node (ref "C32") (pin "2") (pinfunction "2_2") (pintype "passive"))
      (node (ref "R2") (pin "2") (pinfunction "2_2") (pintype "passive"))
      (node (ref "R4") (pin "2") (pinfunction "2_2") (pintype "passive"))
      (node (ref "U2") (pin "5") (pinfunction "5_5") (pintype "passive"))
    )
    (net (code "16") (name "Net-(CLARIFIER-A)") (class "Default")
      (node (ref "CLARIFIER") (pin "3") (pinfunction "A_3") (pintype "passive"))
      (node (ref "R6") (pin "1") (pinfunction "1_1") (pintype "passive"))
    )
    (net (code "17") (name "Net-(CLARIFIER-E)") (class "Default")
      (node (ref "CLARIFIER") (pin "1") (pinfunction "E_1") (pintype "passive"))
      (node (ref "R5") (pin "1") (pinfunction "1_1") (pintype "passive"))
    )
    (net (code "18") (name "Net-(CLARIFIER-S)") (class "Default")
      (node (ref "CLARIFIER") (pin "2") (pinfunction "S_2") (pintype "passive"))
      (node (ref "U2") (pin "7") (pinfunction "7_7") (pintype "passive"))
    )
    (net (code "19") (name "Net-(D4-PadC)") (class "Default")
      (node (ref "D4") (pin "C") (pinfunction "C_C") (pintype "passive"))
      (node (ref "R4") (pin "1") (pinfunction "1_1") (pintype "passive"))
      (node (ref "R5") (pin "2") (pinfunction "2_2") (pintype "passive"))
    )
    (net (code "20") (name "Net-(DISPLAY1-D1_A)") (class "Default")
      (node (ref "C15") (pin "+") (pinfunction "+_+") (pintype "passive"))
      (node (ref "C19") (pin "2") (pinfunction "2_2") (pintype "passive"))
      (node (ref "C33") (pin "+") (pinfunction "+_+") (pintype "passive"))
      (node (ref "C34") (pin "+") (pinfunction "+_+") (pintype "passive"))
      (node (ref "DISPLAY1") (pin "A1") (pinfunction "D1_A_A1") (pintype "input"))
      (node (ref "DISPLAY1") (pin "A2") (pinfunction "D2_A_A2") (pintype "input"))
      (node (ref "DISPLAY1") (pin "A3") (pinfunction "D3_A_A3") (pintype "input"))
      (node (ref "DISPLAY1") (pin "A4") (pinfunction "D4_A_A4") (pintype "input"))
      (node (ref "IC2") (pin "8") (pinfunction "V+_8") (pintype "power_in"))
      (node (ref "LED01") (pin "A") (pinfunction "A_A") (pintype "passive"))
      (node (ref "LED02") (pin "A") (pinfunction "A_A") (pintype "passive"))
      (node (ref "LED03") (pin "A") (pinfunction "A_A") (pintype "passive"))
      (node (ref "LED04") (pin "A") (pinfunction "A_A") (pintype "passive"))
      (node (ref "LED05") (pin "A") (pinfunction "A_A") (pintype "passive"))
      (node (ref "LED06") (pin "A") (pinfunction "A_A") (pintype "passive"))
      (node (ref "LED07") (pin "A") (pinfunction "A_A") (pintype "passive"))
      (node (ref "LED08") (pin "A") (pinfunction "A_A") (pintype "passive"))
      (node (ref "LED09") (pin "A") (pinfunction "A_A") (pintype "passive"))
      (node (ref "LED10") (pin "A") (pinfunction "A_A") (pintype "passive"))
      (node (ref "LED11") (pin "A") (pinfunction "A_A") (pintype "passive"))
      (node (ref "LED12") (pin "A") (pinfunction "A_A") (pintype "passive"))
      (node (ref "LED13") (pin "A") (pinfunction "A_A") (pintype "passive"))
      (node (ref "LED14") (pin "A") (pinfunction "A_A") (pintype "passive"))
      (node (ref "LED15") (pin "A") (pinfunction "A_A") (pintype "passive"))
      (node (ref "LED16") (pin "A") (pinfunction "A_A") (pintype "passive"))
      (node (ref "LED17") (pin "A") (pinfunction "A_A") (pintype "passive"))
      (node (ref "LED18") (pin "A") (pinfunction "A_A") (pintype "passive"))
      (node (ref "LED19") (pin "A") (pinfunction "A_A") (pintype "passive"))
      (node (ref "LED20") (pin "A") (pinfunction "A_A") (pintype "passive"))
      (node (ref "R17") (pin "2") (pinfunction "2_2") (pintype "passive"))
      (node (ref "R18") (pin "2") (pinfunction "2_2") (pintype "passive"))
      (node (ref "U1") (pin "4") (pinfunction "4_4") (pintype "passive"))
    )
    (net (code "21") (name "Net-(DISPLAY1-D1_K)") (class "Default")
      (node (ref "DISPLAY1") (pin "K1") (pinfunction "D1_K_K1") (pintype "input"))
      (node (ref "IC3") (pin "17") (pinfunction "/OUT10_17") (pintype "bidirectional"))
    )
    (net (code "22") (name "Net-(DISPLAY1-D2_K)") (class "Default")
      (node (ref "DISPLAY1") (pin "K2") (pinfunction "D2_K_K2") (pintype "input"))
      (node (ref "IC3") (pin "18") (pinfunction "/OUT11_18") (pintype "bidirectional"))
    )
    (net (code "23") (name "Net-(DISPLAY1-D3_K)") (class "Default")
      (node (ref "DISPLAY1") (pin "K3") (pinfunction "D3_K_K3") (pintype "input"))
      (node (ref "IC4") (pin "17") (pinfunction "/OUT10_17") (pintype "bidirectional"))
    )
    (net (code "24") (name "Net-(DISPLAY1-D4_K)") (class "Default")
      (node (ref "DISPLAY1") (pin "K4") (pinfunction "D4_K_K4") (pintype "input"))
      (node (ref "IC4") (pin "18") (pinfunction "/OUT11_18") (pintype "bidirectional"))
    )
    (net (code "25") (name "Net-(IC1-(A11)PC3)") (class "Default")
      (node (ref "C29") (pin "2") (pinfunction "2_2") (pintype "passive"))
      (node (ref "IC1") (pin "38") (pinfunction "(A11)PC3_38") (pintype "output"))
      (node (ref "PC3") (pin "MP") (pinfunction "MP_MP") (pintype "passive"))
    )
    (net (code "26") (name "Net-(IC1-(A12)PC4)") (class "Default")
      (node (ref "C28") (pin "2") (pinfunction "2_2") (pintype "passive"))
      (node (ref "IC1") (pin "39") (pinfunction "(A12)PC4_39") (pintype "output"))
      (node (ref "PC4") (pin "MP") (pinfunction "MP_MP") (pintype "passive"))
    )
    (net (code "27") (name "Net-(IC1-(A13)PC5)") (class "Default")
      (node (ref "C27") (pin "2") (pinfunction "2_2") (pintype "passive"))
      (node (ref "IC1") (pin "40") (pinfunction "(A13)PC5_40") (pintype "output"))
      (node (ref "PC5") (pin "MP") (pinfunction "MP_MP") (pintype "passive"))
    )
    (net (code "28") (name "Net-(IC1-(AD2)PA2)") (class "Default")
      (node (ref "C26") (pin "2") (pinfunction "2_2") (pintype "passive"))
      (node (ref "IC1") (pin "49") (pinfunction "(AD2)PA2_49") (pintype "bidirectional"))
      (node (ref "R29") (pin "2") (pinfunction "2_2") (pintype "passive"))
      (node (ref "U1") (pin "6") (pinfunction "6_6") (pintype "passive"))
    )
    (net (code "29") (name "Net-(IC1-(AD3)PA3)") (class "Default")
      (node (ref "C11") (pin "2") (pinfunction "2_2") (pintype "passive"))
      (node (ref "IC1") (pin "48") (pinfunction "(AD3)PA3_48") (pintype "bidirectional"))
      (node (ref "U1") (pin "8") (pinfunction "8_8") (pintype "passive"))
    )
    (net (code "30") (name "Net-(IC1-(AD4)PA4)") (class "Default")
      (node (ref "C12") (pin "2") (pinfunction "2_2") (pintype "passive"))
      (node (ref "IC1") (pin "47") (pinfunction "(AD4)PA4_47") (pintype "bidirectional"))
      (node (ref "U1") (pin "10") (pinfunction "10_10") (pintype "passive"))
    )
    (net (code "31") (name "Net-(IC1-(AD5)PA5)") (class "Default")
      (node (ref "C10") (pin "2") (pinfunction "2_2") (pintype "passive"))
      (node (ref "IC1") (pin "46") (pinfunction "(AD5)PA5_46") (pintype "bidirectional"))
      (node (ref "U1") (pin "9") (pinfunction "9_9") (pintype "passive"))
    )
    (net (code "32") (name "Net-(IC1-(AD6)PA6)") (class "Default")
      (node (ref "C9") (pin "2") (pinfunction "2_2") (pintype "passive"))
      (node (ref "IC1") (pin "45") (pinfunction "(AD6)PA6_45") (pintype "bidirectional"))
      (node (ref "U1") (pin "7") (pinfunction "7_7") (pintype "passive"))
    )
    (net (code "33") (name "Net-(IC1-(AD7)PA7)") (class "Default")
      (node (ref "IC1") (pin "44") (pinfunction "(AD7)PA7_44") (pintype "bidirectional"))
      (node (ref "R12") (pin "1") (pinfunction "1_1") (pintype "passive"))
    )
    (net (code "34") (name "Net-(IC1-(IC3{slash}INT7)PE7)") (class "Default")
      (node (ref "C3") (pin "+") (pinfunction "+_+") (pintype "passive"))
      (node (ref "IC1") (pin "9") (pinfunction "(IC3/INT7)PE7_9") (pintype "bidirectional"))
      (node (ref "R25") (pin "1") (pinfunction "1_1") (pintype "passive"))
    )
    (net (code "35") (name "Net-(IC1-(MISO)PB3)") (class "Default")
      (node (ref "IC1") (pin "13") (pinfunction "(MISO)PB3_13") (pintype "bidirectional"))
      (node (ref "IC7") (pin "2") (pinfunction "SO_2") (pintype "bidirectional"))
    )
    (net (code "36") (name "Net-(IC1-(MOSI)PB2)") (class "Default")
      (node (ref "IC1") (pin "12") (pinfunction "(MOSI)PB2_12") (pintype "bidirectional"))
      (node (ref "IC7") (pin "5") (pinfunction "SI_5") (pintype "input"))
    )
    (net (code "37") (name "Net-(IC1-(OC1A)PB5)") (class "Default")
      (node (ref "IC1") (pin "15") (pinfunction "(OC1A)PB5_15") (pintype "bidirectional"))
      (node (ref "U$1") (pin "5") (pinfunction "RW_5") (pintype "bidirectional"))
    )
    (net (code "38") (name "Net-(IC1-(OC3A{slash}AIN1)PE3)") (class "Default")
      (node (ref "IC1") (pin "5") (pinfunction "(OC3A/AIN1)PE3_5") (pintype "bidirectional"))
      (node (ref "SPK") (pin "MP") (pinfunction "MP_MP") (pintype "passive"))
    )
    (net (code "39") (name "Net-(IC1-(OC3B{slash}INT4)PE4)") (class "Default")
      (node (ref "C31") (pin "1") (pinfunction "1_1") (pintype "passive"))
      (node (ref "D3") (pin "C") (pinfunction "C_C") (pintype "passive"))
      (node (ref "IC1") (pin "6") (pinfunction "(OC3B/INT4)PE4_6") (pintype "bidirectional"))
      (node (ref "R23") (pin "2") (pinfunction "2_2") (pintype "passive"))
    )
    (net (code "40") (name "Net-(IC1-(OC3C{slash}INT5)PE5)") (class "Default")
      (node (ref "IC1") (pin "7") (pinfunction "(OC3C/INT5)PE5_7") (pintype "bidirectional"))
      (node (ref "SW01") (pin "3") (pinfunction "3_3") (pintype "passive"))
      (node (ref "SW01") (pin "4") (pinfunction "4_4") (pintype "passive"))
    )
    (net (code "41") (name "Net-(IC1-(SS)PB0)") (class "Default")
      (node (ref "IC1") (pin "10") (pinfunction "(SS)PB0_10") (pintype "bidirectional"))
      (node (ref "IC7") (pin "1") (pinfunction "~{CS}_1") (pintype "input"))
    )
    (net (code "42") (name "Net-(IC1-(T3{slash}INT6)PE6)") (class "Default")
      (node (ref "C30") (pin "1") (pinfunction "1_1") (pintype "passive"))
      (node (ref "IC1") (pin "8") (pinfunction "(T3/INT6)PE6_8") (pintype "bidirectional"))
      (node (ref "PE6") (pin "MP") (pinfunction "MP_MP") (pintype "passive"))
    )
    (net (code "43") (name "Net-(IC1-AVCC)") (class "Default")
      (node (ref "C7") (pin "2") (pinfunction "2_2") (pintype "passive"))
      (node (ref "IC1") (pin "64") (pinfunction "AVCC_64") (pintype "power_in"))
      (node (ref "L1") (pin "1") (pinfunction "1_1") (pintype "passive"))
    )
    (net (code "44") (name "Net-(IC1-PF1(ADC1))") (class "Default")
      (node (ref "IC1") (pin "60") (pinfunction "PF1(ADC1)_60") (pintype "input"))
      (node (ref "SWR/CAL") (pin "3") (pinfunction "A_3") (pintype "passive"))
      (node (ref "U2") (pin "10") (pinfunction "10_10") (pintype "passive"))
    )
    (net (code "45") (name "Net-(IC1-XTAL1)") (class "Default")
      (node (ref "C6") (pin "2") (pinfunction "2_2") (pintype "passive"))
      (node (ref "IC1") (pin "24") (pinfunction "XTAL1_24") (pintype "bidirectional"))
      (node (ref "Q1") (pin "2") (pinfunction "2_2") (pintype "passive"))
    )
    (net (code "46") (name "Net-(IC1-XTAL2)") (class "Default")
      (node (ref "C5") (pin "2") (pinfunction "2_2") (pintype "passive"))
      (node (ref "IC1") (pin "23") (pinfunction "XTAL2_23") (pintype "bidirectional"))
      (node (ref "Q1") (pin "1") (pinfunction "1_1") (pintype "passive"))
    )
    (net (code "47") (name "Net-(IC2A-+IN)") (class "Default")
      (node (ref "C20") (pin "2") (pinfunction "2_2") (pintype "passive"))
      (node (ref "IC2") (pin "3") (pinfunction "+IN_3") (pintype "input"))
      (node (ref "IC2") (pin "6") (pinfunction "-IN_6") (pintype "input"))
      (node (ref "R10") (pin "2") (pinfunction "2_2") (pintype "passive"))
      (node (ref "R17") (pin "1") (pinfunction "1_1") (pintype "passive"))
      (node (ref "UP/DOWN") (pin "MP") (pinfunction "MP_MP") (pintype "passive"))
    )
    (net (code "48") (name "Net-(IC2A--IN)") (class "Default")
      (node (ref "IC2") (pin "2") (pinfunction "-IN_2") (pintype "input"))
      (node (ref "R18") (pin "1") (pinfunction "1_1") (pintype "passive"))
      (node (ref "R19") (pin "2") (pinfunction "2_2") (pintype "passive"))
    )
    (net (code "49") (name "Net-(IC2A-OUT)") (class "Default")
      (node (ref "IC2") (pin "1") (pinfunction "OUT_1") (pintype "output"))
      (node (ref "R11") (pin "2") (pinfunction "2_2") (pintype "passive"))
      (node (ref "R21") (pin "2") (pinfunction "2_2") (pintype "passive"))
    )
    (net (code "50") (name "Net-(IC2B-+IN)") (class "Default")
      (node (ref "IC2") (pin "5") (pinfunction "+IN_5") (pintype "input"))
      (node (ref "R19") (pin "1") (pinfunction "1_1") (pintype "passive"))
      (node (ref "R20") (pin "2") (pinfunction "2_2") (pintype "passive"))
    )
    (net (code "51") (name "Net-(IC2B-OUT)") (class "Default")
      (node (ref "IC2") (pin "7") (pinfunction "OUT_7") (pintype "output"))
      (node (ref "R1") (pin "2") (pinfunction "2_2") (pintype "passive"))
      (node (ref "R22") (pin "2") (pinfunction "2_2") (pintype "passive"))
    )
    (net (code "52") (name "Net-(IC3-REXT)") (class "Default")
      (node (ref "IC3") (pin "1") (pinfunction "REXT_1") (pintype "bidirectional"))
      (node (ref "R3") (pin "2") (pinfunction "2_2") (pintype "passive"))
    )
    (net (code "53") (name "Net-(IC3-{slash}OUT0)") (class "Default")
      (node (ref "IC3") (pin "6") (pinfunction "/OUT0_6") (pintype "bidirectional"))
      (node (ref "LED07") (pin "C") (pinfunction "C_C") (pintype "passive"))
    )
    (net (code "54") (name "Net-(IC3-{slash}OUT1)") (class "Default")
      (node (ref "IC3") (pin "7") (pinfunction "/OUT1_7") (pintype "bidirectional"))
      (node (ref "LED08") (pin "C") (pinfunction "C_C") (pintype "passive"))
    )
    (net (code "55") (name "Net-(IC3-{slash}OUT2)") (class "Default")
      (node (ref "IC3") (pin "8") (pinfunction "/OUT2_8") (pintype "bidirectional"))
      (node (ref "LED05") (pin "C") (pinfunction "C_C") (pintype "passive"))
    )
    (net (code "56") (name "Net-(IC3-{slash}OUT3)") (class "Default")
      (node (ref "IC3") (pin "9") (pinfunction "/OUT3_9") (pintype "bidirectional"))
      (node (ref "LED06") (pin "C") (pinfunction "C_C") (pintype "passive"))
    )
    (net (code "57") (name "Net-(IC3-{slash}OUT4)") (class "Default")
      (node (ref "IC3") (pin "11") (pinfunction "/OUT4_11") (pintype "bidirectional"))
      (node (ref "LED03") (pin "C") (pinfunction "C_C") (pintype "passive"))
    )
    (net (code "58") (name "Net-(IC3-{slash}OUT5)") (class "Default")
      (node (ref "IC3") (pin "12") (pinfunction "/OUT5_12") (pintype "bidirectional"))
      (node (ref "LED04") (pin "C") (pinfunction "C_C") (pintype "passive"))
    )
    (net (code "59") (name "Net-(IC3-{slash}OUT6)") (class "Default")
      (node (ref "IC3") (pin "13") (pinfunction "/OUT6_13") (pintype "bidirectional"))
      (node (ref "LED01") (pin "C") (pinfunction "C_C") (pintype "passive"))
    )
    (net (code "60") (name "Net-(IC3-{slash}OUT7)") (class "Default")
      (node (ref "IC3") (pin "14") (pinfunction "/OUT7_14") (pintype "bidirectional"))
      (node (ref "LED02") (pin "C") (pinfunction "C_C") (pintype "passive"))
    )
    (net (code "61") (name "Net-(IC3-{slash}OUT8)") (class "Default")
      (node (ref "IC3") (pin "15") (pinfunction "/OUT8_15") (pintype "bidirectional"))
      (node (ref "LED09") (pin "C") (pinfunction "C_C") (pintype "passive"))
    )
    (net (code "62") (name "Net-(IC3-{slash}OUT9)") (class "Default")
      (node (ref "IC3") (pin "16") (pinfunction "/OUT9_16") (pintype "bidirectional"))
      (node (ref "LED10") (pin "C") (pinfunction "C_C") (pintype "passive"))
    )
    (net (code "63") (name "Net-(IC3-{slash}RESET)") (class "Default")
      (node (ref "IC3") (pin "25") (pinfunction "/RESET_25") (pintype "bidirectional"))
      (node (ref "R13") (pin "2") (pinfunction "2_2") (pintype "passive"))
    )
    (net (code "64") (name "Net-(IC4-REXT)") (class "Default")
      (node (ref "IC4") (pin "1") (pinfunction "REXT_1") (pintype "bidirectional"))
      (node (ref "R16") (pin "2") (pinfunction "2_2") (pintype "passive"))
    )
    (net (code "65") (name "Net-(IC4-{slash}OUT0)") (class "Default")
      (node (ref "IC4") (pin "6") (pinfunction "/OUT0_6") (pintype "bidirectional"))
      (node (ref "LED17") (pin "C") (pinfunction "C_C") (pintype "passive"))
    )
    (net (code "66") (name "Net-(IC4-{slash}OUT1)") (class "Default")
      (node (ref "IC4") (pin "7") (pinfunction "/OUT1_7") (pintype "bidirectional"))
      (node (ref "LED18") (pin "C") (pinfunction "C_C") (pintype "passive"))
    )
    (net (code "67") (name "Net-(IC4-{slash}OUT2)") (class "Default")
      (node (ref "IC4") (pin "8") (pinfunction "/OUT2_8") (pintype "bidirectional"))
      (node (ref "LED15") (pin "C") (pinfunction "C_C") (pintype "passive"))
    )
    (net (code "68") (name "Net-(IC4-{slash}OUT3)") (class "Default")
      (node (ref "IC4") (pin "9") (pinfunction "/OUT3_9") (pintype "bidirectional"))
      (node (ref "LED16") (pin "C") (pinfunction "C_C") (pintype "passive"))
    )
    (net (code "69") (name "Net-(IC4-{slash}OUT4)") (class "Default")
      (node (ref "IC4") (pin "11") (pinfunction "/OUT4_11") (pintype "bidirectional"))
      (node (ref "LED11") (pin "C") (pinfunction "C_C") (pintype "passive"))
    )
    (net (code "70") (name "Net-(IC4-{slash}OUT5)") (class "Default")
      (node (ref "IC4") (pin "12") (pinfunction "/OUT5_12") (pintype "bidirectional"))
      (node (ref "LED12") (pin "C") (pinfunction "C_C") (pintype "passive"))
    )
    (net (code "71") (name "Net-(IC4-{slash}OUT6)") (class "Default")
      (node (ref "IC4") (pin "13") (pinfunction "/OUT6_13") (pintype "bidirectional"))
      (node (ref "LED13") (pin "C") (pinfunction "C_C") (pintype "passive"))
    )
    (net (code "72") (name "Net-(IC4-{slash}OUT7)") (class "Default")
      (node (ref "IC4") (pin "14") (pinfunction "/OUT7_14") (pintype "bidirectional"))
      (node (ref "LED14") (pin "C") (pinfunction "C_C") (pintype "passive"))
    )
    (net (code "73") (name "Net-(IC4-{slash}OUT8)") (class "Default")
      (node (ref "IC4") (pin "15") (pinfunction "/OUT8_15") (pintype "bidirectional"))
      (node (ref "LED19") (pin "C") (pinfunction "C_C") (pintype "passive"))
    )
    (net (code "74") (name "Net-(IC4-{slash}OUT9)") (class "Default")
      (node (ref "IC4") (pin "16") (pinfunction "/OUT9_16") (pintype "bidirectional"))
      (node (ref "LED20") (pin "C") (pinfunction "C_C") (pintype "passive"))
    )
    (net (code "75") (name "Net-(IC4-{slash}RESET)") (class "Default")
      (node (ref "IC4") (pin "25") (pinfunction "/RESET_25") (pintype "bidirectional"))
      (node (ref "R33") (pin "2") (pinfunction "2_2") (pintype "passive"))
    )
    (net (code "76") (name "Net-(IC5-I{slash}O0.0)") (class "Default")
      (node (ref "IC5") (pin "4") (pinfunction "I/O0.0_4") (pintype "bidirectional"))
      (node (ref "SW13") (pin "3") (pinfunction "3_3") (pintype "passive"))
      (node (ref "SW13") (pin "4") (pinfunction "4_4") (pintype "passive"))
    )
    (net (code "77") (name "Net-(IC5-I{slash}O0.1)") (class "Default")
      (node (ref "IC5") (pin "5") (pinfunction "I/O0.1_5") (pintype "bidirectional"))
      (node (ref "SW14") (pin "3") (pinfunction "3_3") (pintype "passive"))
      (node (ref "SW14") (pin "4") (pinfunction "4_4") (pintype "passive"))
    )
    (net (code "78") (name "Net-(IC5-I{slash}O0.2)") (class "Default")
      (node (ref "IC5") (pin "6") (pinfunction "I/O0.2_6") (pintype "bidirectional"))
      (node (ref "SW15") (pin "3") (pinfunction "3_3") (pintype "passive"))
      (node (ref "SW15") (pin "4") (pinfunction "4_4") (pintype "passive"))
    )
    (net (code "79") (name "Net-(IC5-I{slash}O0.6)") (class "Default")
      (node (ref "IC5") (pin "10") (pinfunction "I/O0.6_10") (pintype "bidirectional"))
      (node (ref "T5") (pin "E") (pinfunction "E_E") (pintype "passive"))
    )
    (net (code "80") (name "Net-(IC5-I{slash}O0.7)") (class "Default")
      (node (ref "IC5") (pin "11") (pinfunction "I/O0.7_11") (pintype "bidirectional"))
      (node (ref "T6") (pin "E") (pinfunction "E_E") (pintype "passive"))
    )
    (net (code "81") (name "Net-(IC5-I{slash}O1.0)") (class "Default")
      (node (ref "IC5") (pin "13") (pinfunction "I/O1.0_13") (pintype "bidirectional"))
      (node (ref "SW17") (pin "3") (pinfunction "3_3") (pintype "passive"))
      (node (ref "SW17") (pin "4") (pinfunction "4_4") (pintype "passive"))
    )
    (net (code "82") (name "Net-(IC5-I{slash}O1.1)") (class "Default")
      (node (ref "C21") (pin "2") (pinfunction "2_2") (pintype "passive"))
      (node (ref "IC5") (pin "14") (pinfunction "I/O1.1_14") (pintype "bidirectional"))
      (node (ref "SW22") (pin "B") (pinfunction "B_B") (pintype "passive"))
    )
    (net (code "83") (name "Net-(IC5-I{slash}O1.2)") (class "Default")
      (node (ref "C22") (pin "2") (pinfunction "2_2") (pintype "passive"))
      (node (ref "IC5") (pin "15") (pinfunction "I/O1.2_15") (pintype "bidirectional"))
      (node (ref "SW22") (pin "A") (pinfunction "A_A") (pintype "passive"))
    )
    (net (code "84") (name "Net-(IC5-I{slash}O1.3)") (class "Default")
      (node (ref "IC5") (pin "16") (pinfunction "I/O1.3_16") (pintype "bidirectional"))
      (node (ref "SW16") (pin "3") (pinfunction "3_3") (pintype "passive"))
      (node (ref "SW16") (pin "4") (pinfunction "4_4") (pintype "passive"))
    )
    (net (code "85") (name "Net-(IC5-I{slash}O1.4)") (class "Default")
      (node (ref "IC5") (pin "17") (pinfunction "I/O1.4_17") (pintype "bidirectional"))
      (node (ref "SW19") (pin "3") (pinfunction "3_3") (pintype "passive"))
      (node (ref "SW19") (pin "4") (pinfunction "4_4") (pintype "passive"))
    )
    (net (code "86") (name "Net-(IC5-I{slash}O1.5)") (class "Default")
      (node (ref "IC5") (pin "18") (pinfunction "I/O1.5_18") (pintype "bidirectional"))
      (node (ref "SW18") (pin "3") (pinfunction "3_3") (pintype "passive"))
      (node (ref "SW18") (pin "4") (pinfunction "4_4") (pintype "passive"))
    )
    (net (code "87") (name "Net-(IC5-I{slash}O1.6)") (class "Default")
      (node (ref "IC5") (pin "19") (pinfunction "I/O1.6_19") (pintype "bidirectional"))
      (node (ref "SW21") (pin "3") (pinfunction "3_3") (pintype "passive"))
      (node (ref "SW21") (pin "4") (pinfunction "4_4") (pintype "passive"))
    )
    (net (code "88") (name "Net-(IC5-I{slash}O1.7)") (class "Default")
      (node (ref "IC5") (pin "20") (pinfunction "I/O1.7_20") (pintype "bidirectional"))
      (node (ref "SW20") (pin "3") (pinfunction "3_3") (pintype "passive"))
      (node (ref "SW20") (pin "4") (pinfunction "4_4") (pintype "passive"))
    )
    (net (code "89") (name "Net-(IC5-~{INT})") (class "Default")
      (node (ref "IC5") (pin "1") (pinfunction "~{INT}_1") (pintype "output"))
      (node (ref "IC6") (pin "1") (pinfunction "~{INT}_1") (pintype "output"))
      (node (ref "R25") (pin "2") (pinfunction "2_2") (pintype "passive"))
    )
    (net (code "90") (name "Net-(IC6-I{slash}O0.0)") (class "Default")
      (node (ref "IC6") (pin "4") (pinfunction "I/O0.0_4") (pintype "bidirectional"))
      (node (ref "SW12") (pin "3") (pinfunction "3_3") (pintype "passive"))
      (node (ref "SW12") (pin "4") (pinfunction "4_4") (pintype "passive"))
    )
    (net (code "91") (name "Net-(IC6-I{slash}O0.1)") (class "Default")
      (node (ref "IC6") (pin "5") (pinfunction "I/O0.1_5") (pintype "bidirectional"))
      (node (ref "SW11") (pin "3") (pinfunction "3_3") (pintype "passive"))
      (node (ref "SW11") (pin "4") (pinfunction "4_4") (pintype "passive"))
    )
    (net (code "92") (name "Net-(IC6-I{slash}O0.2)") (class "Default")
      (node (ref "IC6") (pin "6") (pinfunction "I/O0.2_6") (pintype "bidirectional"))
      (node (ref "SW10") (pin "3") (pinfunction "3_3") (pintype "passive"))
      (node (ref "SW10") (pin "4") (pinfunction "4_4") (pintype "passive"))
    )
    (net (code "93") (name "Net-(IC6-I{slash}O0.3)") (class "Default")
      (node (ref "IC6") (pin "7") (pinfunction "I/O0.3_7") (pintype "bidirectional"))
      (node (ref "SW02") (pin "3") (pinfunction "3_3") (pintype "passive"))
      (node (ref "SW02") (pin "4") (pinfunction "4_4") (pintype "passive"))
    )
    (net (code "94") (name "Net-(IC6-I{slash}O0.4)") (class "Default")
      (node (ref "IC6") (pin "8") (pinfunction "I/O0.4_8") (pintype "bidirectional"))
      (node (ref "SW03") (pin "3") (pinfunction "3_3") (pintype "passive"))
      (node (ref "SW03") (pin "4") (pinfunction "4_4") (pintype "passive"))
    )
    (net (code "95") (name "Net-(IC6-I{slash}O0.5)") (class "Default")
      (node (ref "IC6") (pin "9") (pinfunction "I/O0.5_9") (pintype "bidirectional"))
      (node (ref "SW04") (pin "3") (pinfunction "3_3") (pintype "passive"))
      (node (ref "SW04") (pin "4") (pinfunction "4_4") (pintype "passive"))
    )
    (net (code "96") (name "Net-(IC6-I{slash}O0.6)") (class "Default")
      (node (ref "IC6") (pin "10") (pinfunction "I/O0.6_10") (pintype "bidirectional"))
      (node (ref "SW05") (pin "3") (pinfunction "3_3") (pintype "passive"))
      (node (ref "SW05") (pin "4") (pinfunction "4_4") (pintype "passive"))
    )
    (net (code "97") (name "Net-(IC6-I{slash}O1.0)") (class "Default")
      (node (ref "IC6") (pin "13") (pinfunction "I/O1.0_13") (pintype "bidirectional"))
      (node (ref "SW06") (pin "3") (pinfunction "3_3") (pintype "passive"))
      (node (ref "SW06") (pin "4") (pinfunction "4_4") (pintype "passive"))
    )
    (net (code "98") (name "Net-(IC6-I{slash}O1.1)") (class "Default")
      (node (ref "IC6") (pin "14") (pinfunction "I/O1.1_14") (pintype "bidirectional"))
      (node (ref "R8") (pin "1") (pinfunction "1_1") (pintype "passive"))
      (node (ref "R9") (pin "2") (pinfunction "2_2") (pintype "passive"))
    )
    (net (code "99") (name "Net-(IC6-I{slash}O1.2)") (class "Default")
      (node (ref "IC6") (pin "15") (pinfunction "I/O1.2_15") (pintype "bidirectional"))
      (node (ref "SW07") (pin "3") (pinfunction "3_3") (pintype "passive"))
      (node (ref "SW07") (pin "4") (pinfunction "4_4") (pintype "passive"))
    )
    (net (code "100") (name "Net-(IC6-I{slash}O1.3)") (class "Default")
      (node (ref "IC6") (pin "16") (pinfunction "I/O1.3_16") (pintype "bidirectional"))
      (node (ref "SW08") (pin "3") (pinfunction "3_3") (pintype "passive"))
      (node (ref "SW08") (pin "4") (pinfunction "4_4") (pintype "passive"))
    )
    (net (code "101") (name "Net-(IC6-I{slash}O1.4)") (class "Default")
      (node (ref "IC6") (pin "17") (pinfunction "I/O1.4_17") (pintype "bidirectional"))
      (node (ref "SW09") (pin "3") (pinfunction "3_3") (pintype "passive"))
      (node (ref "SW09") (pin "4") (pinfunction "4_4") (pintype "passive"))
    )
    (net (code "102") (name "Net-(IC8-BP0)") (class "Default")
      (node (ref "DISPLAY1") (pin "COM1") (pinfunction "COM1_COM1") (pintype "input"))
      (node (ref "IC8") (pin "25") (pinfunction "BP0_25") (pintype "output"))
    )
    (net (code "103") (name "Net-(IC8-BP1)") (class "Default")
      (node (ref "DISPLAY1") (pin "COM2") (pinfunction "COM2_COM2") (pintype "input"))
      (node (ref "IC8") (pin "26") (pinfunction "BP1_26") (pintype "output"))
    )
    (net (code "104") (name "Net-(IC8-BP2)") (class "Default")
      (node (ref "DISPLAY1") (pin "COM3") (pinfunction "COM3_COM3") (pintype "input"))
      (node (ref "IC8") (pin "27") (pinfunction "BP2_27") (pintype "output"))
    )
    (net (code "105") (name "Net-(IC8-S0)") (class "Default")
      (node (ref "DISPLAY1") (pin "SEG01") (pinfunction "SEG01_SEG01") (pintype "input"))
      (node (ref "IC8") (pin "29") (pinfunction "S0_29") (pintype "output"))
    )
    (net (code "106") (name "Net-(IC8-S1)") (class "Default")
      (node (ref "DISPLAY1") (pin "SEG02") (pinfunction "SEG02_SEG02") (pintype "input"))
      (node (ref "IC8") (pin "30") (pinfunction "S1_30") (pintype "output"))
    )
    (net (code "107") (name "Net-(IC8-S2)") (class "Default")
      (node (ref "DISPLAY1") (pin "SEG03") (pinfunction "SEG03_SEG03") (pintype "input"))
      (node (ref "IC8") (pin "31") (pinfunction "S2_31") (pintype "output"))
    )
    (net (code "108") (name "Net-(IC8-S3)") (class "Default")
      (node (ref "DISPLAY1") (pin "SEG04") (pinfunction "SEG04_SEG04") (pintype "input"))
      (node (ref "IC8") (pin "32") (pinfunction "S3_32") (pintype "output"))
    )
    (net (code "109") (name "Net-(IC8-S4)") (class "Default")
      (node (ref "DISPLAY1") (pin "SEG05") (pinfunction "SEG05_SEG05") (pintype "input"))
      (node (ref "IC8") (pin "34") (pinfunction "S4_34") (pintype "output"))
    )
    (net (code "110") (name "Net-(IC8-S5)") (class "Default")
      (node (ref "DISPLAY1") (pin "SEG06") (pinfunction "SEG06_SEG06") (pintype "input"))
      (node (ref "IC8") (pin "35") (pinfunction "S5_35") (pintype "output"))
    )
    (net (code "111") (name "Net-(IC8-S6)") (class "Default")
      (node (ref "DISPLAY1") (pin "SEG07") (pinfunction "SEG07_SEG07") (pintype "input"))
      (node (ref "IC8") (pin "36") (pinfunction "S6_36") (pintype "output"))
    )
    (net (code "112") (name "Net-(IC8-S7)") (class "Default")
      (node (ref "DISPLAY1") (pin "SEG08") (pinfunction "SEG08_SEG08") (pintype "input"))
      (node (ref "IC8") (pin "37") (pinfunction "S7_37") (pintype "output"))
    )
    (net (code "113") (name "Net-(IC8-S8)") (class "Default")
      (node (ref "DISPLAY1") (pin "SEG09") (pinfunction "SEG09_SEG09") (pintype "input"))
      (node (ref "IC8") (pin "38") (pinfunction "S8_38") (pintype "output"))
    )
    (net (code "114") (name "Net-(IC8-S9)") (class "Default")
      (node (ref "DISPLAY1") (pin "SEG10") (pinfunction "SEG10_SEG10") (pintype "input"))
      (node (ref "IC8") (pin "39") (pinfunction "S9_39") (pintype "output"))
    )
    (net (code "115") (name "Net-(IC8-S10)") (class "Default")
      (node (ref "DISPLAY1") (pin "SEG11") (pinfunction "SEG11_SEG11") (pintype "input"))
      (node (ref "IC8") (pin "40") (pinfunction "S10_40") (pintype "output"))
    )
    (net (code "116") (name "Net-(IC8-S11)") (class "Default")
      (node (ref "DISPLAY1") (pin "SEG12") (pinfunction "SEG12_SEG12") (pintype "input"))
      (node (ref "IC8") (pin "41") (pinfunction "S11_41") (pintype "output"))
    )
    (net (code "117") (name "Net-(IC8-S12)") (class "Default")
      (node (ref "DISPLAY1") (pin "SEG13") (pinfunction "SEG13_SEG13") (pintype "input"))
      (node (ref "IC8") (pin "42") (pinfunction "S12_42") (pintype "output"))
    )
    (net (code "118") (name "Net-(IC8-S13)") (class "Default")
      (node (ref "DISPLAY1") (pin "SEG14") (pinfunction "SEG14_SEG14") (pintype "input"))
      (node (ref "IC8") (pin "43") (pinfunction "S13_43") (pintype "output"))
    )
    (net (code "119") (name "Net-(IC8-S14)") (class "Default")
      (node (ref "DISPLAY1") (pin "SEG15") (pinfunction "SEG15_SEG15") (pintype "input"))
      (node (ref "IC8") (pin "44") (pinfunction "S14_44") (pintype "output"))
    )
    (net (code "120") (name "Net-(IC8-S15)") (class "Default")
      (node (ref "DISPLAY1") (pin "SEG16") (pinfunction "SEG16_SEG16") (pintype "input"))
      (node (ref "IC8") (pin "45") (pinfunction "S15_45") (pintype "output"))
    )
    (net (code "121") (name "Net-(IC8-S16)") (class "Default")
      (node (ref "DISPLAY1") (pin "SEG17") (pinfunction "SEG17_SEG17") (pintype "input"))
      (node (ref "IC8") (pin "46") (pinfunction "S16_46") (pintype "output"))
    )
    (net (code "122") (name "Net-(IC8-S17)") (class "Default")
      (node (ref "DISPLAY1") (pin "SEG18") (pinfunction "SEG18_SEG18") (pintype "input"))
      (node (ref "IC8") (pin "47") (pinfunction "S17_47") (pintype "output"))
    )
    (net (code "123") (name "Net-(IC8-S18)") (class "Default")
      (node (ref "DISPLAY1") (pin "SEG19") (pinfunction "SEG19_SEG19") (pintype "input"))
      (node (ref "IC8") (pin "49") (pinfunction "S18_49") (pintype "output"))
    )
    (net (code "124") (name "Net-(IC8-S19)") (class "Default")
      (node (ref "DISPLAY1") (pin "SEG20") (pinfunction "SEG20_SEG20") (pintype "input"))
      (node (ref "IC8") (pin "50") (pinfunction "S19_50") (pintype "output"))
    )
    (net (code "125") (name "Net-(IC8-S20)") (class "Default")
      (node (ref "DISPLAY1") (pin "SEG21") (pinfunction "SEG21_SEG21") (pintype "input"))
      (node (ref "IC8") (pin "51") (pinfunction "S20_51") (pintype "output"))
    )
    (net (code "126") (name "Net-(IC8-S21)") (class "Default")
      (node (ref "DISPLAY1") (pin "SEG22") (pinfunction "SEG22_SEG22") (pintype "input"))
      (node (ref "IC8") (pin "52") (pinfunction "S21_52") (pintype "output"))
    )
    (net (code "127") (name "Net-(IC8-S22)") (class "Default")
      (node (ref "DISPLAY1") (pin "SEG23") (pinfunction "SEG23_SEG23") (pintype "input"))
      (node (ref "IC8") (pin "53") (pinfunction "S22_53") (pintype "output"))
    )
    (net (code "128") (name "Net-(IC8-S23)") (class "Default")
      (node (ref "DISPLAY1") (pin "SEG24") (pinfunction "SEG24_SEG24") (pintype "input"))
      (node (ref "IC8") (pin "54") (pinfunction "S23_54") (pintype "output"))
    )
    (net (code "129") (name "Net-(IC8-S24)") (class "Default")
      (node (ref "DISPLAY1") (pin "SEG25") (pinfunction "SEG25_SEG25") (pintype "input"))
      (node (ref "IC8") (pin "55") (pinfunction "S24_55") (pintype "output"))
    )
    (net (code "130") (name "Net-(IC8-S25)") (class "Default")
      (node (ref "DISPLAY1") (pin "SEG26") (pinfunction "SEG26_SEG26") (pintype "input"))
      (node (ref "IC8") (pin "56") (pinfunction "S25_56") (pintype "output"))
    )
    (net (code "131") (name "Net-(IC8-S26)") (class "Default")
      (node (ref "DISPLAY1") (pin "SEG27") (pinfunction "SEG27_SEG27") (pintype "input"))
      (node (ref "IC8") (pin "57") (pinfunction "S26_57") (pintype "output"))
    )
    (net (code "132") (name "Net-(IC8-S27)") (class "Default")
      (node (ref "DISPLAY1") (pin "SEG28") (pinfunction "SEG28_SEG28") (pintype "input"))
      (node (ref "IC8") (pin "58") (pinfunction "S27_58") (pintype "output"))
    )
    (net (code "133") (name "Net-(IC8-S28)") (class "Default")
      (node (ref "DISPLAY1") (pin "SEG29") (pinfunction "SEG29_SEG29") (pintype "input"))
      (node (ref "IC8") (pin "59") (pinfunction "S28_59") (pintype "output"))
    )
    (net (code "134") (name "Net-(IC8-S29)") (class "Default")
      (node (ref "DISPLAY1") (pin "SEG30") (pinfunction "SEG30_SEG30") (pintype "input"))
      (node (ref "IC8") (pin "60") (pinfunction "S29_60") (pintype "output"))
    )
    (net (code "135") (name "Net-(IC8-S30)") (class "Default")
      (node (ref "DISPLAY1") (pin "SEG31") (pinfunction "SEG31_SEG31") (pintype "input"))
      (node (ref "IC8") (pin "61") (pinfunction "S30_61") (pintype "output"))
    )
    (net (code "136") (name "Net-(IC8-S31)") (class "Default")
      (node (ref "DISPLAY1") (pin "SEG32") (pinfunction "SEG32_SEG32") (pintype "input"))
      (node (ref "IC8") (pin "62") (pinfunction "S31_62") (pintype "output"))
    )
    (net (code "137") (name "Net-(IC8-S32)") (class "Default")
      (node (ref "DISPLAY1") (pin "SEG33") (pinfunction "SEG33_SEG33") (pintype "input"))
      (node (ref "IC8") (pin "63") (pinfunction "S32_63") (pintype "output"))
    )
    (net (code "138") (name "Net-(IC8-VLCD)") (class "Default")
      (node (ref "IC8") (pin "21") (pinfunction "VLCD_21") (pintype "power_in"))
      (node (ref "R30") (pin "2") (pinfunction "2_2") (pintype "passive"))
    )
    (net (code "139") (name "Net-(R1-Pad1)") (class "Default")
      (node (ref "R1") (pin "1") (pinfunction "1_1") (pintype "passive"))
      (node (ref "T6") (pin "B") (pinfunction "B_B") (pintype "passive"))
    )
    (net (code "140") (name "Net-(R7-Pad2)") (class "Default")
      (node (ref "R7") (pin "2") (pinfunction "2_2") (pintype "passive"))
      (node (ref "U2") (pin "8") (pinfunction "8_8") (pintype "passive"))
    )
    (net (code "141") (name "Net-(R11-Pad1)") (class "Default")
      (node (ref "R11") (pin "1") (pinfunction "1_1") (pintype "passive"))
      (node (ref "T5") (pin "B") (pinfunction "B_B") (pintype "passive"))
    )
    (net (code "142") (name "Net-(RF-POWER-S)") (class "Default")
      (node (ref "RF-POWER") (pin "2") (pinfunction "S_2") (pintype "passive"))
      (node (ref "U2") (pin "6") (pinfunction "6_6") (pintype "passive"))
    )
    (net (code "143") (name "Net-(SQUELCH-A)") (class "Default")
      (node (ref "R2") (pin "1") (pinfunction "1_1") (pintype "passive"))
      (node (ref "SQUELCH") (pin "3") (pinfunction "A_3") (pintype "passive"))
    )
    (net (code "144") (name "Net-(SQUELCH-S)") (class "Default")
      (node (ref "SQUELCH") (pin "2") (pinfunction "S_2") (pintype "passive"))
      (node (ref "U2") (pin "4") (pinfunction "4_4") (pintype "passive"))
    )
    (net (code "145") (name "Net-(SWR/CAL-S)") (class "Default")
      (node (ref "R7") (pin "1") (pinfunction "1_1") (pintype "passive"))
      (node (ref "SWR/CAL") (pin "2") (pinfunction "S_2") (pintype "passive"))
    )
    (net (code "146") (name "Net-(T1-B)") (class "Default")
      (node (ref "R12") (pin "2") (pinfunction "2_2") (pintype "passive"))
      (node (ref "T1") (pin "1") (pinfunction "B_1") (pintype "passive"))
    )
    (net (code "147") (name "Net-(T1-C)") (class "Default")
      (node (ref "T1") (pin "4") (pinfunction "C_4") (pintype "passive"))
      (node (ref "U1") (pin "3") (pinfunction "3_3") (pintype "passive"))
    )
    (net (code "148") (name "Net-(T4-B)") (class "Default")
      (node (ref "R15") (pin "1") (pinfunction "1_1") (pintype "passive"))
      (node (ref "T4") (pin "1") (pinfunction "B_1") (pintype "passive"))
    )
    (net (code "149") (name "Net-(T4-C)") (class "Default")
      (node (ref "R32") (pin "2") (pinfunction "2_2") (pintype "passive"))
      (node (ref "T4") (pin "4") (pinfunction "C_4") (pintype "passive"))
    )
    (net (code "150") (name "Net-(U$1-RH)") (class "Default")
      (node (ref "R28") (pin "1") (pinfunction "1_1") (pintype "passive"))
      (node (ref "U$1") (pin "7") (pinfunction "RH_7") (pintype "bidirectional"))
    )
    (net (code "151") (name "Net-(VOLUME-A)") (class "Default")
      (node (ref "U2") (pin "3") (pinfunction "3_3") (pintype "passive"))
      (node (ref "VOLUME") (pin "3") (pinfunction "A_3") (pintype "passive"))
    )
    (net (code "152") (name "Net-(VOLUME-E)") (class "Default")
      (node (ref "U2") (pin "2") (pinfunction "2_2") (pintype "passive"))
      (node (ref "VOLUME") (pin "1") (pinfunction "E_1") (pintype "passive"))
    )
    (net (code "153") (name "Net-(VOLUME-S)") (class "Default")
      (node (ref "U2") (pin "1") (pinfunction "1_1") (pintype "passive"))
      (node (ref "VOLUME") (pin "2") (pinfunction "S_2") (pintype "passive"))
    )
    (net (code "154") (name "VCC") (class "Default")
      (node (ref "5V") (pin "MP") (pinfunction "MP_MP") (pintype "passive"))
      (node (ref "C13") (pin "2") (pinfunction "2_2") (pintype "passive"))
      (node (ref "C14") (pin "2") (pinfunction "2_2") (pintype "passive"))
      (node (ref "C17") (pin "2") (pinfunction "2_2") (pintype "passive"))
      (node (ref "C23") (pin "2") (pinfunction "2_2") (pintype "passive"))
      (node (ref "C24") (pin "2") (pinfunction "2_2") (pintype "passive"))
      (node (ref "C35") (pin "2") (pinfunction "2_2") (pintype "passive"))
      (node (ref "C4") (pin "+") (pinfunction "+_+") (pintype "passive"))
      (node (ref "D2") (pin "C") (pinfunction "C_C") (pintype "passive"))
      (node (ref "IC3") (pin "28") (pinfunction "VCC_28") (pintype "bidirectional"))
      (node (ref "IC4") (pin "2") (pinfunction "A0_2") (pintype "bidirectional"))
      (node (ref "IC4") (pin "28") (pinfunction "VCC_28") (pintype "bidirectional"))
      (node (ref "IC5") (pin "21") (pinfunction "A0_21") (pintype "input"))
      (node (ref "IC5") (pin "24") (pinfunction "VDD_24") (pintype "power_in"))
      (node (ref "IC6") (pin "24") (pinfunction "VDD_24") (pintype "power_in"))
      (node (ref "IC8") (pin "14") (pinfunction "VDD_14") (pintype "power_in"))
      (node (ref "R13") (pin "1") (pinfunction "1_1") (pintype "passive"))
      (node (ref "R21") (pin "1") (pinfunction "1_1") (pintype "passive"))
      (node (ref "R22") (pin "1") (pinfunction "1_1") (pintype "passive"))
      (node (ref "R26") (pin "2") (pinfunction "2_2") (pintype "passive"))
      (node (ref "R27") (pin "2") (pinfunction "2_2") (pintype "passive"))
      (node (ref "R33") (pin "1") (pinfunction "1_1") (pintype "passive"))
      (node (ref "R9") (pin "1") (pinfunction "1_1") (pintype "passive"))
      (node (ref "U$1") (pin "1") (pinfunction "WP_1") (pintype "bidirectional"))
      (node (ref "U$1") (pin "8") (pinfunction "VCC_8") (pintype "power_in"))
      (node (ref "U3") (pin "1") (pinfunction "1_1") (pintype "passive"))
    )
    (net (code "155") (name "VCCMEM") (class "Default")
      (node (ref "C16") (pin "2") (pinfunction "2_2") (pintype "passive"))
      (node (ref "C8") (pin "2") (pinfunction "2_2") (pintype "passive"))
      (node (ref "D1") (pin "C") (pinfunction "C_C") (pintype "passive"))
      (node (ref "GC+") (pin "MP") (pinfunction "MP_MP") (pintype "passive"))
      (node (ref "IC1") (pin "21") (pinfunction "VCC_21") (pintype "power_in"))
      (node (ref "IC1") (pin "52") (pinfunction "VCC_52") (pintype "power_in"))
      (node (ref "IC7") (pin "3") (pinfunction "~{WP}_3") (pintype "input"))
      (node (ref "IC7") (pin "7") (pinfunction "~{HOLD}_7") (pintype "input"))
      (node (ref "IC7") (pin "8") (pinfunction "VCC_8") (pintype "power_in"))
      (node (ref "L1") (pin "2") (pinfunction "2_2") (pintype "passive"))
    )
    (net (code "156") (name "unconnected-(IC1-(A8)PC0-Pad35)") (class "Default")
      (node (ref "IC1") (pin "35") (pinfunction "(A8)PC0_35") (pintype "output"))
    )
    (net (code "157") (name "unconnected-(IC1-(A9)PC1-Pad36)") (class "Default")
      (node (ref "IC1") (pin "36") (pinfunction "(A9)PC1_36") (pintype "output"))
    )
    (net (code "158") (name "unconnected-(IC1-(A10)PC2-Pad37)") (class "Default")
      (node (ref "IC1") (pin "37") (pinfunction "(A10)PC2_37") (pintype "output"))
    )
    (net (code "159") (name "unconnected-(IC1-(A14)PC6-Pad41)") (class "Default")
      (node (ref "IC1") (pin "41") (pinfunction "(A14)PC6_41") (pintype "output"))
    )
    (net (code "160") (name "unconnected-(IC1-(A15)PC7-Pad42)") (class "Default")
      (node (ref "IC1") (pin "42") (pinfunction "(A15)PC7_42") (pintype "output"))
    )
    (net (code "161") (name "unconnected-(IC1-(AD0)PA0-Pad51)") (class "Default")
      (node (ref "IC1") (pin "51") (pinfunction "(AD0)PA0_51") (pintype "bidirectional"))
    )
    (net (code "162") (name "unconnected-(IC1-(AD1)PA1-Pad50)") (class "Default")
      (node (ref "IC1") (pin "50") (pinfunction "(AD1)PA1_50") (pintype "bidirectional"))
    )
    (net (code "163") (name "unconnected-(IC1-(IC1)PD4-Pad29)") (class "Default")
      (node (ref "IC1") (pin "29") (pinfunction "(IC1)PD4_29") (pintype "bidirectional"))
    )
    (net (code "164") (name "unconnected-(IC1-(OC0)PB4-Pad14)") (class "Default")
      (node (ref "IC1") (pin "14") (pinfunction "(OC0)PB4_14") (pintype "bidirectional"))
    )
    (net (code "165") (name "unconnected-(IC1-(OC1B)PB6-Pad16)") (class "Default")
      (node (ref "IC1") (pin "16") (pinfunction "(OC1B)PB6_16") (pintype "bidirectional"))
    )
    (net (code "166") (name "unconnected-(IC1-(OC2{slash}OC1C)PB7-Pad17)") (class "Default")
      (node (ref "IC1") (pin "17") (pinfunction "(OC2/OC1C)PB7_17") (pintype "bidirectional"))
    )
    (net (code "167") (name "unconnected-(IC1-(T1)PD6-Pad31)") (class "Default")
      (node (ref "IC1") (pin "31") (pinfunction "(T1)PD6_31") (pintype "bidirectional"))
    )
    (net (code "168") (name "unconnected-(IC1-(T2)PD7-Pad32)") (class "Default")
      (node (ref "IC1") (pin "32") (pinfunction "(T2)PD7_32") (pintype "bidirectional"))
    )
    (net (code "169") (name "unconnected-(IC1-(XCK0{slash}AIN0)PE2-Pad4)") (class "Default")
      (node (ref "IC1") (pin "4") (pinfunction "(XCK0/AIN0)PE2_4") (pintype "bidirectional"))
    )
    (net (code "170") (name "unconnected-(IC1-(XCK1)PD5-Pad30)") (class "Default")
      (node (ref "IC1") (pin "30") (pinfunction "(XCK1)PD5_30") (pintype "bidirectional"))
    )
    (net (code "171") (name "unconnected-(IC1-AREF-Pad62)") (class "Default")
      (node (ref "IC1") (pin "62") (pinfunction "AREF_62") (pintype "passive"))
    )
    (net (code "172") (name "unconnected-(IC1-PEN-Pad1)") (class "Default")
      (node (ref "IC1") (pin "1") (pinfunction "PEN_1") (pintype "input"))
    )
    (net (code "173") (name "unconnected-(IC1-PF2(ADC2)-Pad59)") (class "Default")
      (node (ref "IC1") (pin "59") (pinfunction "PF2(ADC2)_59") (pintype "input"))
    )
    (net (code "174") (name "unconnected-(IC1-PF3(ADC3)-Pad58)") (class "Default")
      (node (ref "IC1") (pin "58") (pinfunction "PF3(ADC3)_58") (pintype "input"))
    )
    (net (code "175") (name "unconnected-(IC1-PF4(ADC4{slash}TCK)-Pad57)") (class "Default")
      (node (ref "IC1") (pin "57") (pinfunction "PF4(ADC4/TCK)_57") (pintype "input"))
    )
    (net (code "176") (name "unconnected-(IC1-PF5(ADC5{slash}TMS)-Pad56)") (class "Default")
      (node (ref "IC1") (pin "56") (pinfunction "PF5(ADC5/TMS)_56") (pintype "input"))
    )
    (net (code "177") (name "unconnected-(IC1-PF6(ADC6{slash}TDO)-Pad55)") (class "Default")
      (node (ref "IC1") (pin "55") (pinfunction "PF6(ADC6/TDO)_55") (pintype "input"))
    )
    (net (code "178") (name "unconnected-(IC1-PF7(ADC7{slash}TDI)-Pad54)") (class "Default")
      (node (ref "IC1") (pin "54") (pinfunction "PF7(ADC7/TDI)_54") (pintype "input"))
    )
    (net (code "179") (name "unconnected-(IC1-PG0(WR)-Pad33)") (class "Default")
      (node (ref "IC1") (pin "33") (pinfunction "PG0(WR)_33") (pintype "bidirectional"))
    )
    (net (code "180") (name "unconnected-(IC1-PG1(RD)-Pad34)") (class "Default")
      (node (ref "IC1") (pin "34") (pinfunction "PG1(RD)_34") (pintype "bidirectional"))
    )
    (net (code "181") (name "unconnected-(IC1-PG2(ALE)-Pad43)") (class "Default")
      (node (ref "IC1") (pin "43") (pinfunction "PG2(ALE)_43") (pintype "bidirectional"))
    )
    (net (code "182") (name "unconnected-(IC1-PG3(TOSC2)-Pad18)") (class "Default")
      (node (ref "IC1") (pin "18") (pinfunction "PG3(TOSC2)_18") (pintype "bidirectional"))
    )
    (net (code "183") (name "unconnected-(IC1-PG4(TOSC1)-Pad19)") (class "Default")
      (node (ref "IC1") (pin "19") (pinfunction "PG4(TOSC1)_19") (pintype "bidirectional"))
    )
    (net (code "184") (name "unconnected-(IC3-{slash}OUT12-Pad20)") (class "Default")
      (node (ref "IC3") (pin "20") (pinfunction "/OUT12_20") (pintype "bidirectional"))
    )
    (net (code "185") (name "unconnected-(IC3-{slash}OUT13-Pad21)") (class "Default")
      (node (ref "IC3") (pin "21") (pinfunction "/OUT13_21") (pintype "bidirectional"))
    )
    (net (code "186") (name "unconnected-(IC3-{slash}OUT14-Pad22)") (class "Default")
      (node (ref "IC3") (pin "22") (pinfunction "/OUT14_22") (pintype "bidirectional"))
    )
    (net (code "187") (name "unconnected-(IC3-{slash}OUT15-Pad23)") (class "Default")
      (node (ref "IC3") (pin "23") (pinfunction "/OUT15_23") (pintype "bidirectional"))
    )
    (net (code "188") (name "unconnected-(IC4-{slash}OUT12-Pad20)") (class "Default")
      (node (ref "IC4") (pin "20") (pinfunction "/OUT12_20") (pintype "bidirectional"))
    )
    (net (code "189") (name "unconnected-(IC4-{slash}OUT13-Pad21)") (class "Default")
      (node (ref "IC4") (pin "21") (pinfunction "/OUT13_21") (pintype "bidirectional"))
    )
    (net (code "190") (name "unconnected-(IC4-{slash}OUT14-Pad22)") (class "Default")
      (node (ref "IC4") (pin "22") (pinfunction "/OUT14_22") (pintype "bidirectional"))
    )
    (net (code "191") (name "unconnected-(IC4-{slash}OUT15-Pad23)") (class "Default")
      (node (ref "IC4") (pin "23") (pinfunction "/OUT15_23") (pintype "bidirectional"))
    )
    (net (code "192") (name "unconnected-(IC5-I{slash}O0.3-Pad7)") (class "Default")
      (node (ref "IC5") (pin "7") (pinfunction "I/O0.3_7") (pintype "bidirectional"))
    )
    (net (code "193") (name "unconnected-(IC5-I{slash}O0.4-Pad8)") (class "Default")
      (node (ref "IC5") (pin "8") (pinfunction "I/O0.4_8") (pintype "bidirectional"))
    )
    (net (code "194") (name "unconnected-(IC5-I{slash}O0.5-Pad9)") (class "Default")
      (node (ref "IC5") (pin "9") (pinfunction "I/O0.5_9") (pintype "bidirectional"))
    )
    (net (code "195") (name "unconnected-(IC6-I{slash}O0.7-Pad11)") (class "Default")
      (node (ref "IC6") (pin "11") (pinfunction "I/O0.7_11") (pintype "bidirectional"))
    )
    (net (code "196") (name "unconnected-(IC6-I{slash}O1.5-Pad18)") (class "Default")
      (node (ref "IC6") (pin "18") (pinfunction "I/O1.5_18") (pintype "bidirectional"))
    )
    (net (code "197") (name "unconnected-(IC6-I{slash}O1.6-Pad19)") (class "Default")
      (node (ref "IC6") (pin "19") (pinfunction "I/O1.6_19") (pintype "bidirectional"))
    )
    (net (code "198") (name "unconnected-(IC6-I{slash}O1.7-Pad20)") (class "Default")
      (node (ref "IC6") (pin "20") (pinfunction "I/O1.7_20") (pintype "bidirectional"))
    )
    (net (code "199") (name "unconnected-(IC8-BP3-Pad28)") (class "Default")
      (node (ref "IC8") (pin "28") (pinfunction "BP3_28") (pintype "output"))
    )
    (net (code "200") (name "unconnected-(IC8-CLK-Pad13)") (class "Default")
      (node (ref "IC8") (pin "13") (pinfunction "CLK_13") (pintype "bidirectional"))
    )
    (net (code "201") (name "unconnected-(IC8-S33-Pad64)") (class "Default")
      (node (ref "IC8") (pin "64") (pinfunction "S33_64") (pintype "output"))
    )
    (net (code "202") (name "unconnected-(IC8-S34-Pad2)") (class "Default")
      (node (ref "IC8") (pin "2") (pinfunction "S34_2") (pintype "output"))
    )
    (net (code "203") (name "unconnected-(IC8-S35-Pad3)") (class "Default")
      (node (ref "IC8") (pin "3") (pinfunction "S35_3") (pintype "output"))
    )
    (net (code "204") (name "unconnected-(IC8-S36-Pad4)") (class "Default")
      (node (ref "IC8") (pin "4") (pinfunction "S36_4") (pintype "output"))
    )
    (net (code "205") (name "unconnected-(IC8-S37-Pad5)") (class "Default")
      (node (ref "IC8") (pin "5") (pinfunction "S37_5") (pintype "output"))
    )
    (net (code "206") (name "unconnected-(IC8-S38-Pad6)") (class "Default")
      (node (ref "IC8") (pin "6") (pinfunction "S38_6") (pintype "output"))
    )
    (net (code "207") (name "unconnected-(IC8-S39-Pad7)") (class "Default")
      (node (ref "IC8") (pin "7") (pinfunction "S39_7") (pintype "output"))
    )
    (net (code "208") (name "unconnected-(IC8-SYNC-Pad12)") (class "Default")
      (node (ref "IC8") (pin "12") (pinfunction "SYNC_12") (pintype "bidirectional"))
    )
    (net (code "209") (name "unconnected-(RF-POWER-A-Pad3)") (class "Default")
      (node (ref "RF-POWER") (pin "3") (pinfunction "A_3") (pintype "passive"))
    )
    (net (code "210") (name "unconnected-(U1-Pad11)") (class "Default")
      (node (ref "U1") (pin "11") (pinfunction "11_11") (pintype "passive"))
    )
    (net (code "211") (name "unconnected-(U1-Pad12)") (class "Default")
      (node (ref "U1") (pin "12") (pinfunction "12_12") (pintype "passive"))
    )
    (net (code "212") (name "unconnected-(U2-Pad11)") (class "Default")
      (node (ref "U2") (pin "11") (pinfunction "11_11") (pintype "passive"))
    )
    (net (code "213") (name "unconnected-(U2-Pad12)") (class "Default")
      (node (ref "U2") (pin "12") (pinfunction "12_12") (pintype "passive"))
    )
    (net (code "214") (name "unconnected-(U3-Pad7)") (class "Default")
      (node (ref "U3") (pin "7") (pinfunction "7_7") (pintype "passive"))
    )
    (net (code "215") (name "unconnected-(U3-Pad8)") (class "Default")
      (node (ref "U3") (pin "8") (pinfunction "8_8") (pintype "passive"))
    )
  )
)
